# Comim_OBC-v_3_0.net
KiCad netlist of a schematic drawn in EAGLE
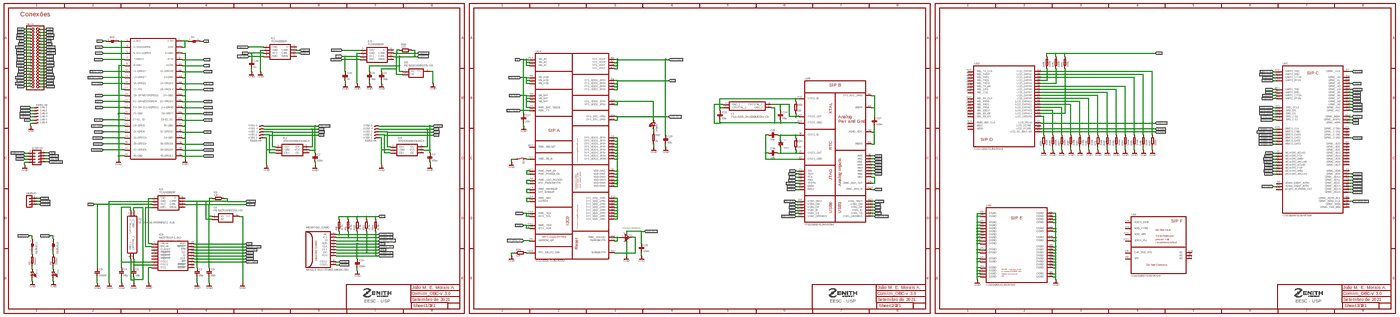
[diagram p0: schematic, sheet 1, overview]
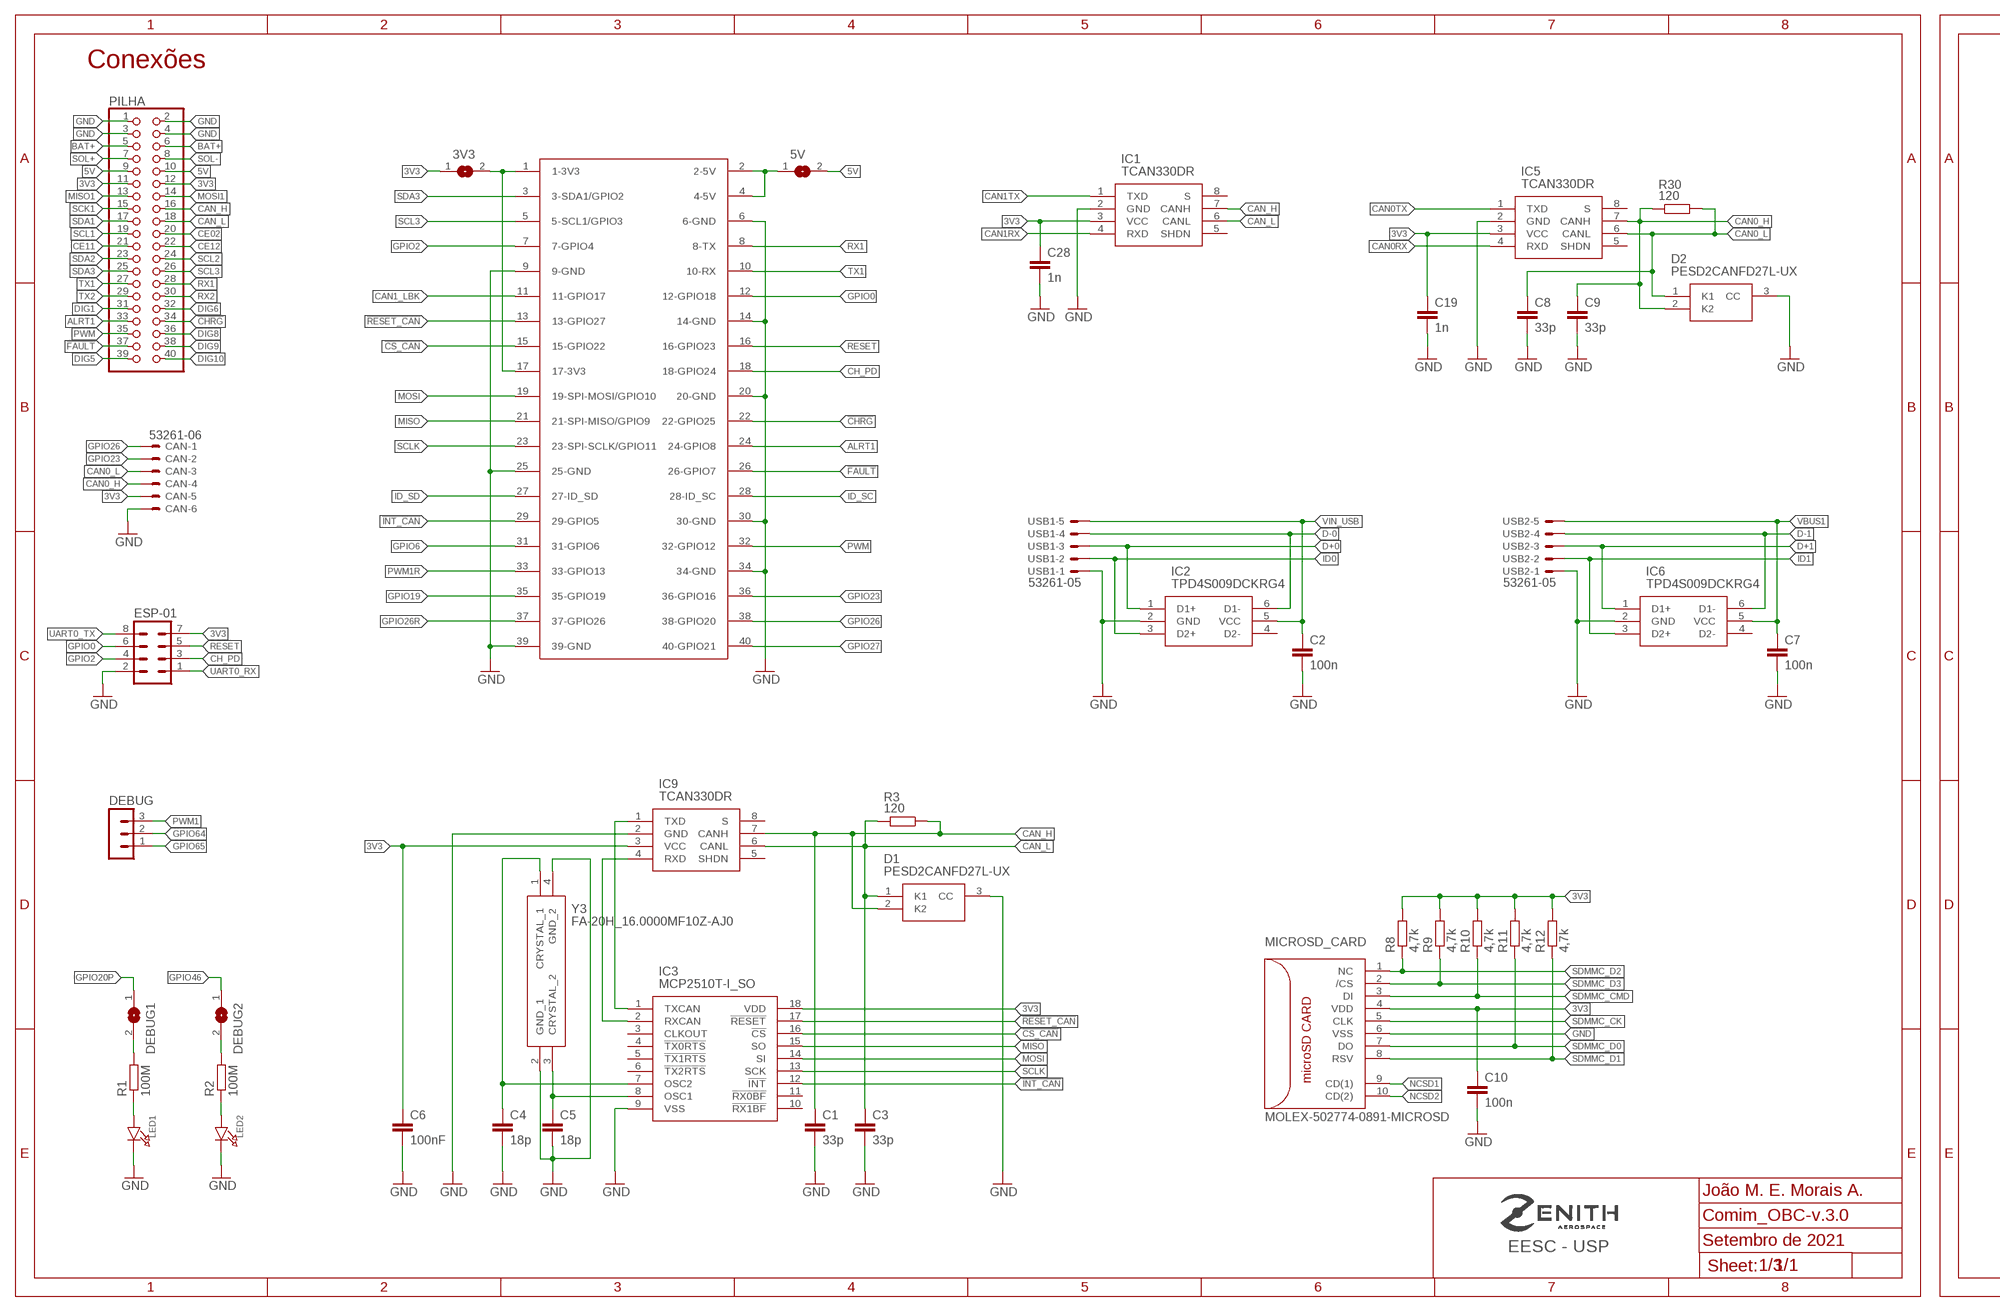
[diagram p1: schematic, sheet 1, part 1 of 4]
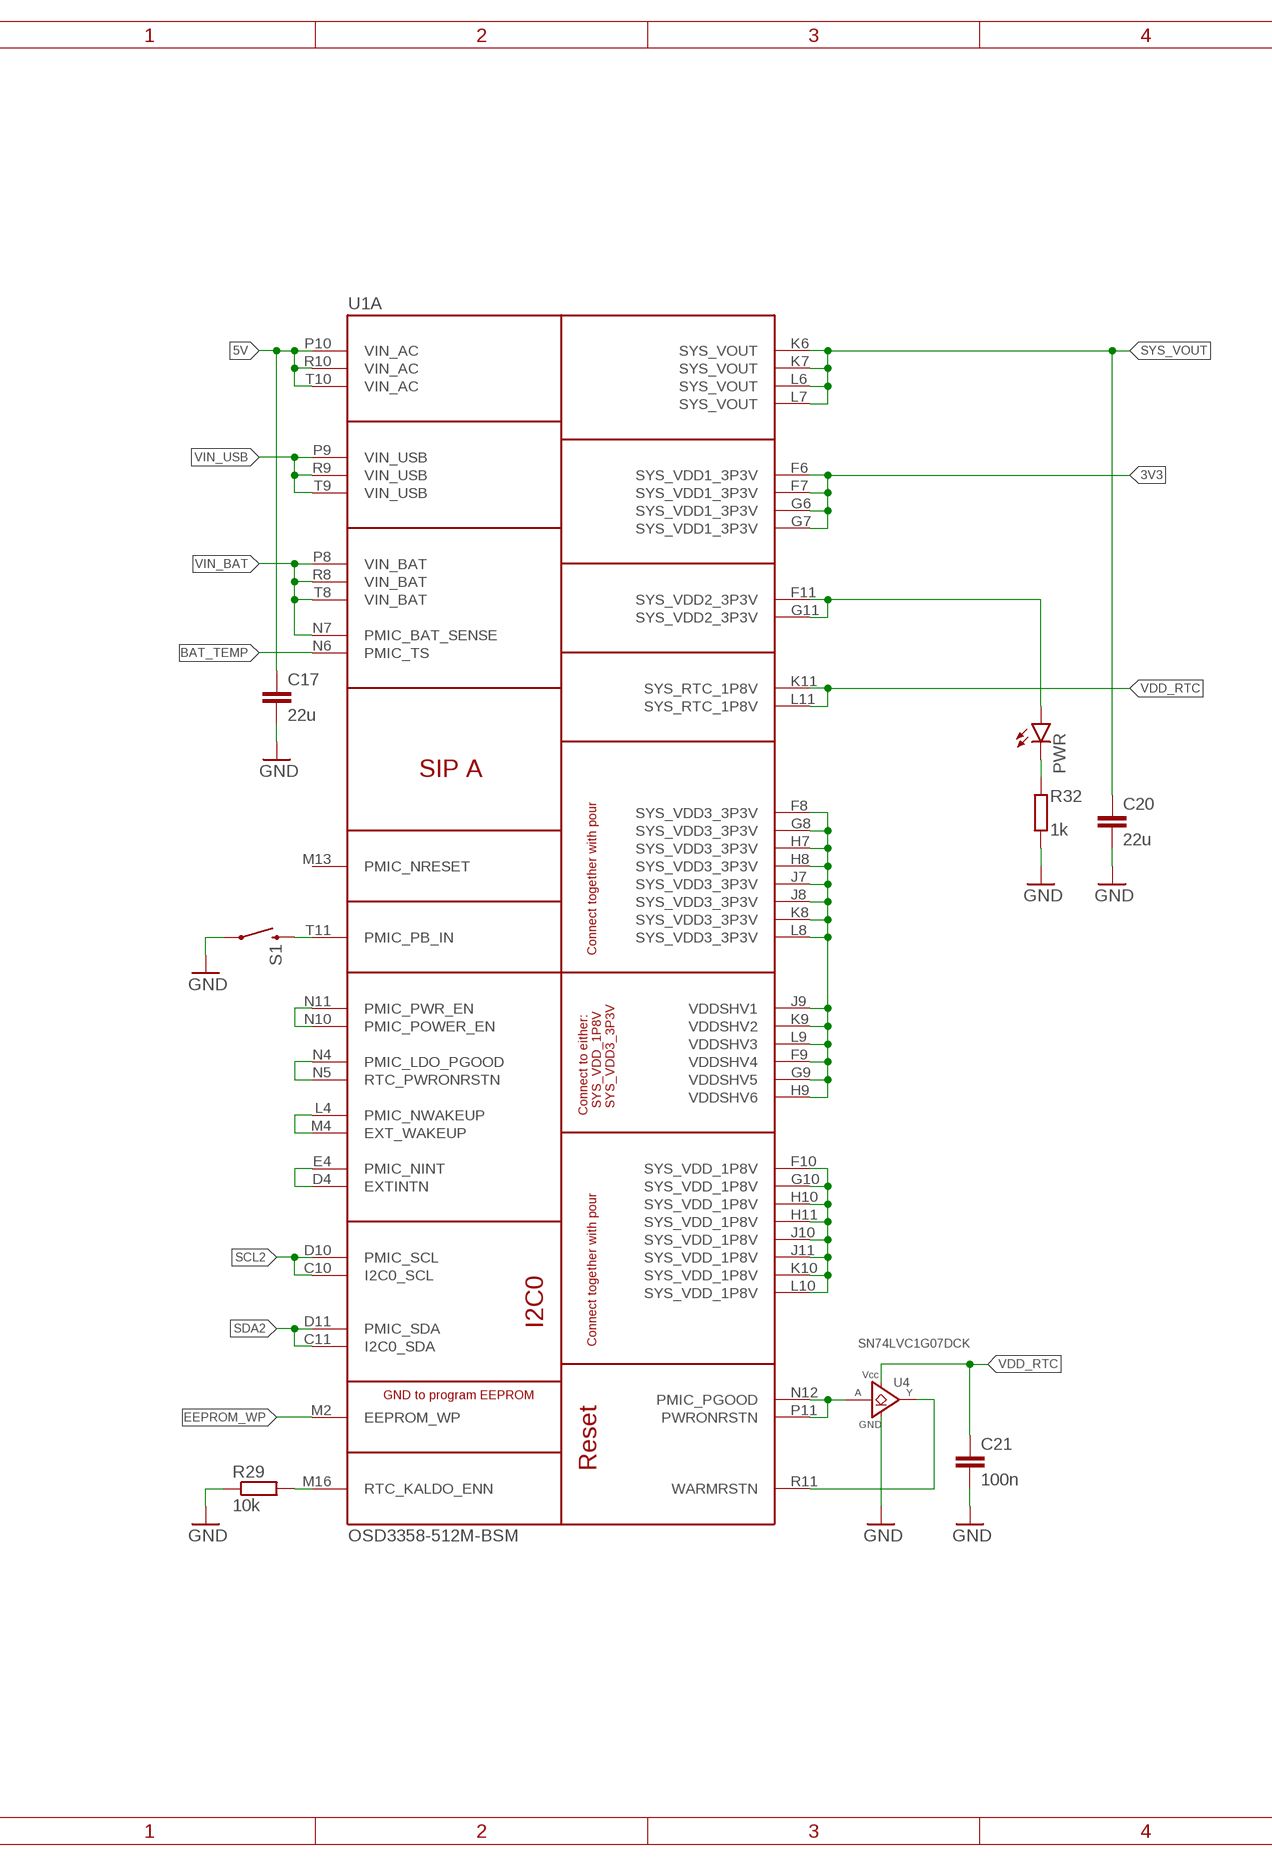
[diagram p2: schematic, sheet 1, part 2 of 4]
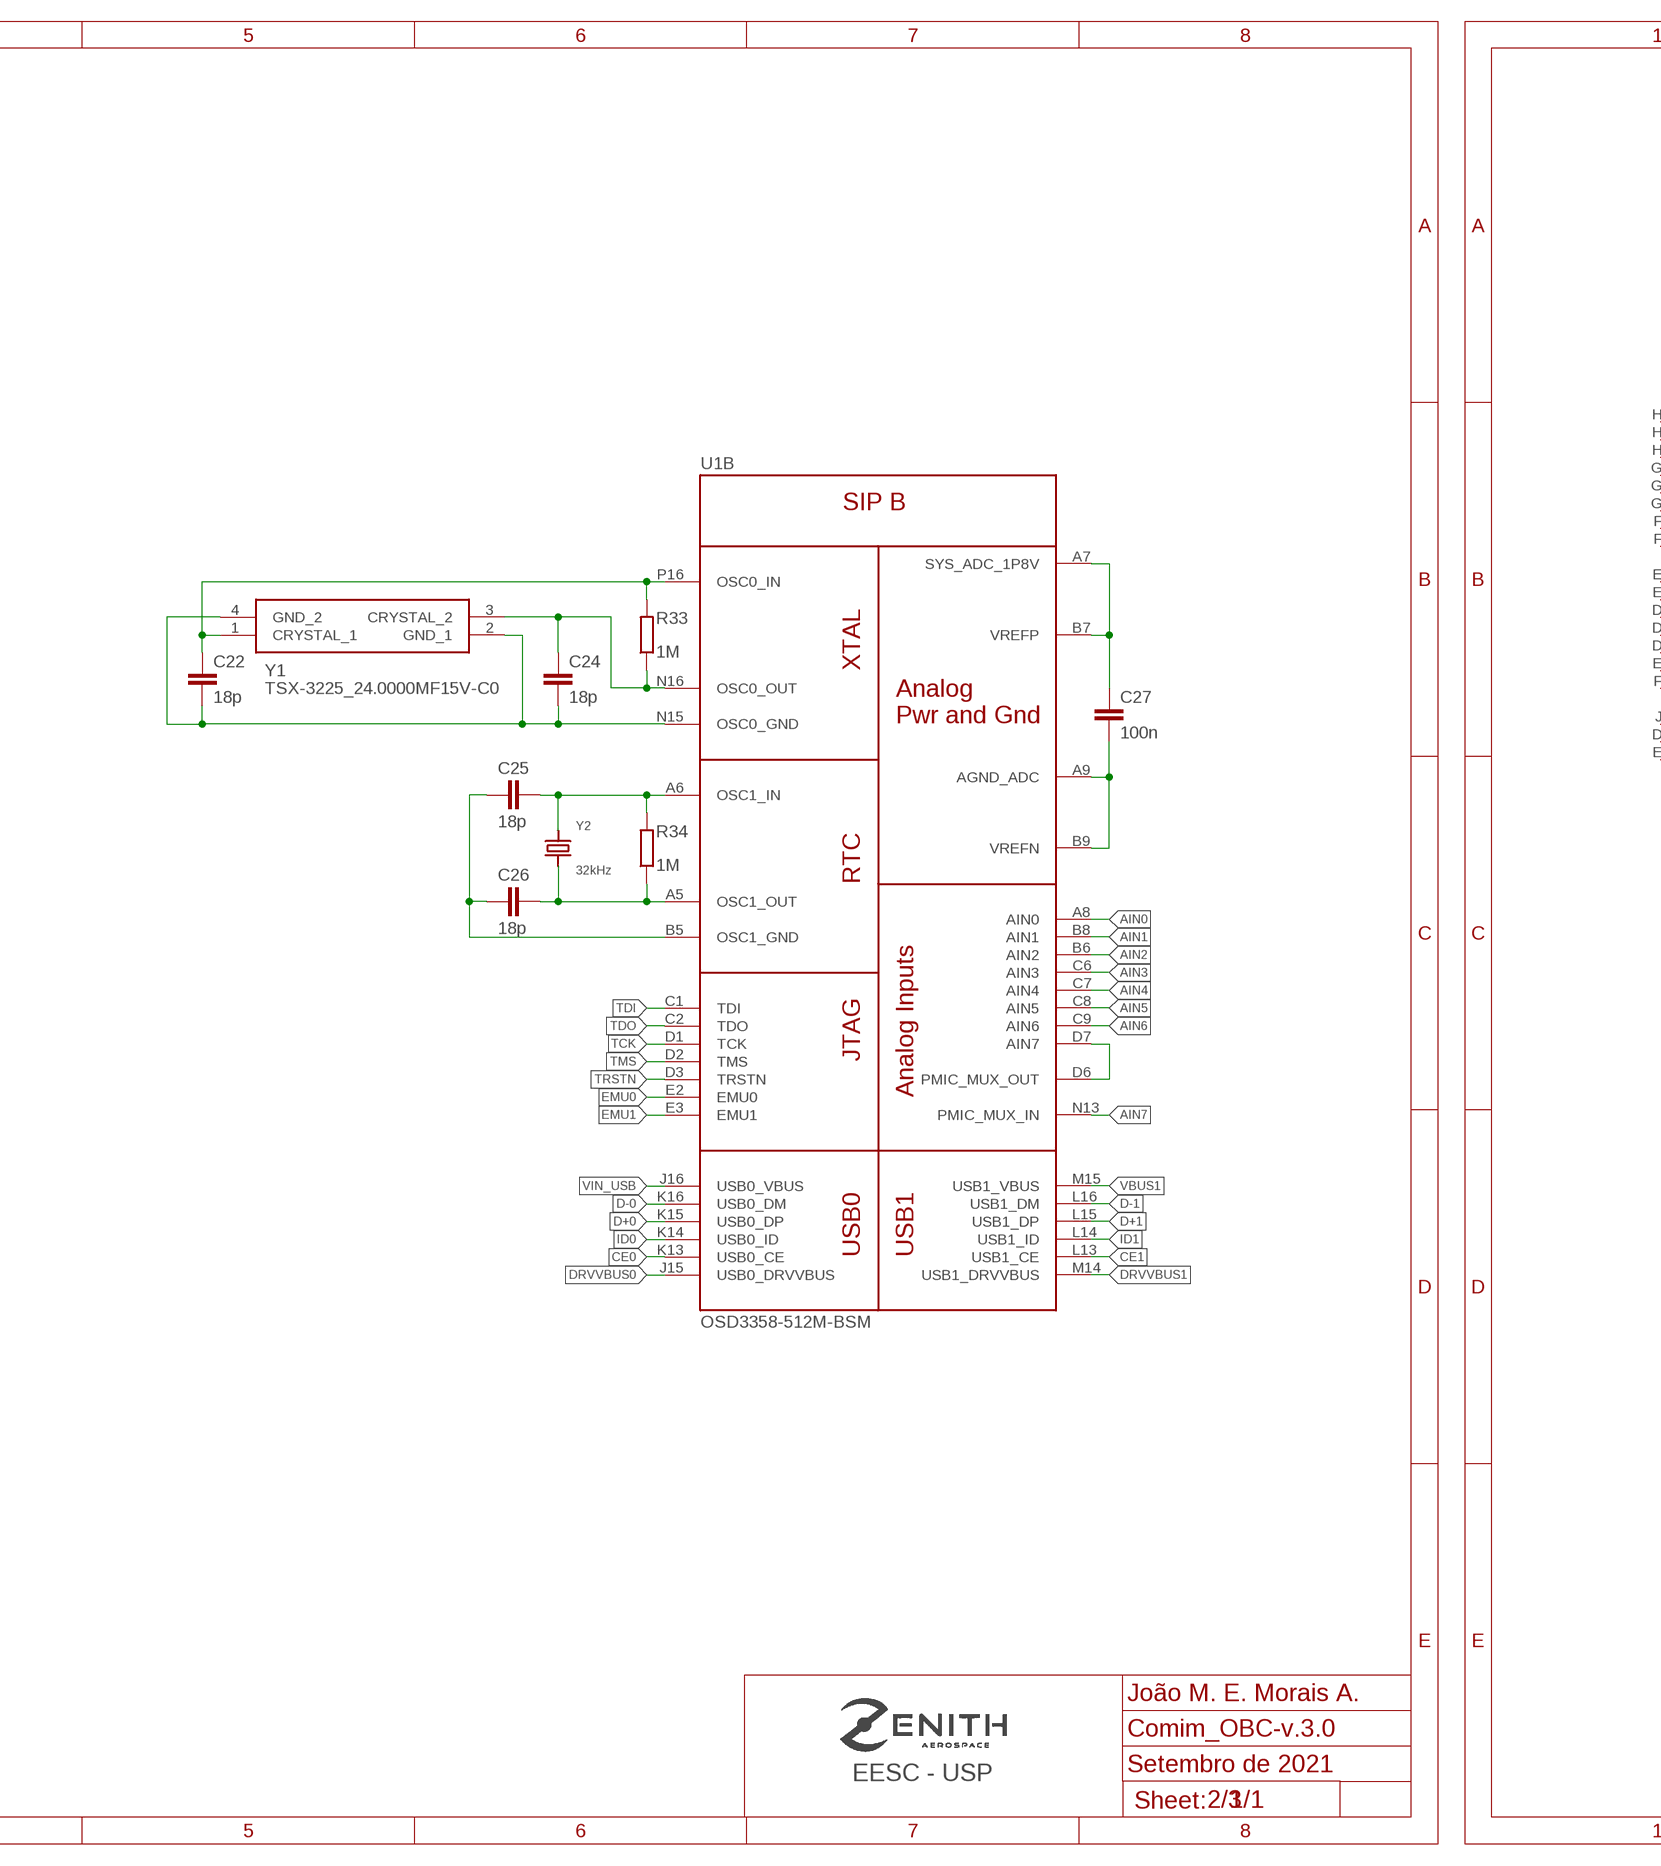
[diagram p3: schematic, sheet 1, part 3 of 4]
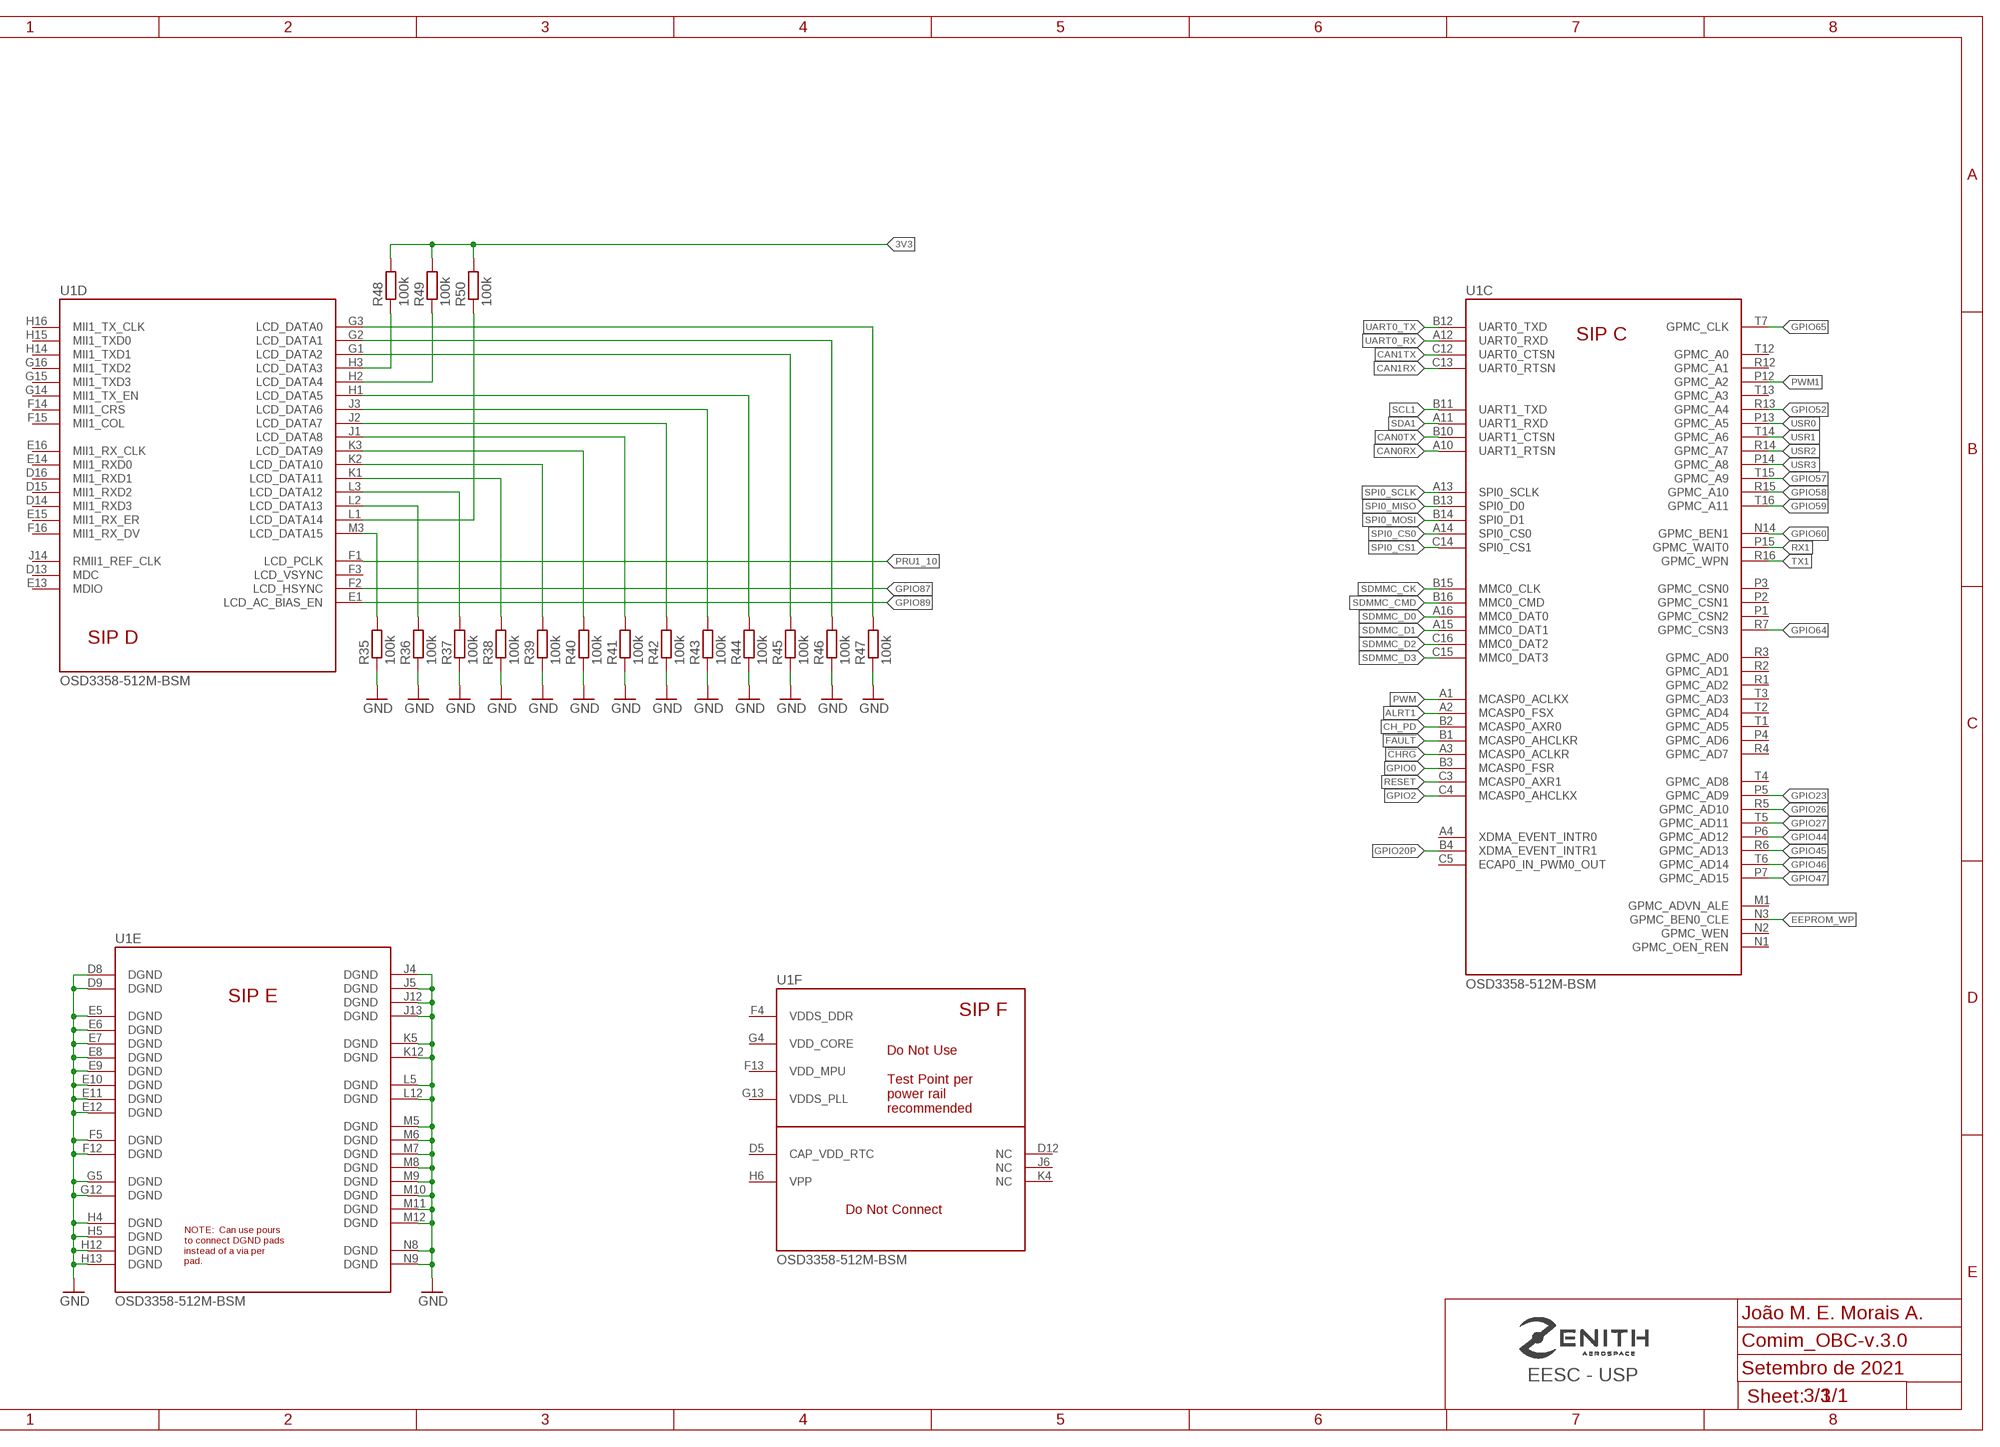
[diagram p4: schematic, sheet 1, part 4 of 4]

(export (version "E")
  (design (tool "Eeschema 10.0.6"))
  (components
    (comp (ref "3V3") (value "SJ") (footprint "eagle-import:SJ") (libsource (lib "eagle-import") (part "SJ")))
    (comp (ref "5V") (value "SJ") (footprint "eagle-import:SJ") (libsource (lib "eagle-import") (part "SJ")))
    (comp (ref "C1")
      (value "33p")
      (footprint "eagle-import:C0805")
      (libsource (lib "eagle-import") (part "C-EUC0805"))
    )
    (comp (ref "C2")
      (value "100n")
      (footprint "eagle-import:C0805")
      (libsource (lib "eagle-import") (part "C-EUC0805"))
    )
    (comp (ref "C3")
      (value "33p")
      (footprint "eagle-import:C0805")
      (libsource (lib "eagle-import") (part "C-EUC0805"))
    )
    (comp (ref "C4")
      (value "18p")
      (footprint "eagle-import:C0805")
      (libsource (lib "eagle-import") (part "C-EUC0805"))
    )
    (comp (ref "C5")
      (value "18p")
      (footprint "eagle-import:C0805")
      (libsource (lib "eagle-import") (part "C-EUC0805"))
    )
    (comp (ref "C6")
      (value "100nF")
      (footprint "eagle-import:C0805")
      (libsource (lib "eagle-import") (part "C-EUC0805"))
    )
    (comp (ref "C7")
      (value "100n")
      (footprint "eagle-import:C0805")
      (libsource (lib "eagle-import") (part "C-EUC0805"))
    )
    (comp (ref "C8")
      (value "33p")
      (footprint "eagle-import:C0805")
      (libsource (lib "eagle-import") (part "C-EUC0805"))
    )
    (comp (ref "C9")
      (value "33p")
      (footprint "eagle-import:C0805")
      (libsource (lib "eagle-import") (part "C-EUC0805"))
    )
    (comp (ref "C10")
      (value "100n")
      (footprint "eagle-import:C0805")
      (libsource (lib "eagle-import") (part "C-EUC0805"))
    )
    (comp (ref "C17")
      (value "22u")
      (footprint "eagle-import:C0805")
      (libsource (lib "eagle-import") (part "C-EUC0805"))
    )
    (comp (ref "C19")
      (value "1n")
      (footprint "eagle-import:C0805")
      (libsource (lib "eagle-import") (part "C-EUC0805"))
    )
    (comp (ref "C20")
      (value "22u")
      (footprint "eagle-import:C0805")
      (libsource (lib "eagle-import") (part "C-EUC0805"))
    )
    (comp (ref "C21")
      (value "100n")
      (footprint "eagle-import:C0805")
      (libsource (lib "eagle-import") (part "C-EUC0805"))
    )
    (comp (ref "C22")
      (value "18p")
      (footprint "eagle-import:C0805")
      (libsource (lib "eagle-import") (part "C-EUC0805"))
    )
    (comp (ref "C24")
      (value "18p")
      (footprint "eagle-import:C0805")
      (libsource (lib "eagle-import") (part "C-EUC0805"))
    )
    (comp (ref "C25")
      (value "18p")
      (footprint "eagle-import:C0805")
      (libsource (lib "eagle-import") (part "C-EUC0805"))
    )
    (comp (ref "C26")
      (value "18p")
      (footprint "eagle-import:C0805")
      (libsource (lib "eagle-import") (part "C-EUC0805"))
    )
    (comp (ref "C27")
      (value "100n")
      (footprint "eagle-import:C0805")
      (libsource (lib "eagle-import") (part "C-EUC0805"))
    )
    (comp (ref "C28")
      (value "1n")
      (footprint "eagle-import:C0805")
      (libsource (lib "eagle-import") (part "C-EUC0805"))
    )
    (comp (ref "CAN")
      (value "53261-06")
      (footprint "eagle-import:53261-06")
      (fields (field (name "MF") "MOLEX"))
      (libsource (lib "eagle-import") (part "53?-06261"))
    )
    (comp (ref "D1")
      (value "PESD2CANFD27L-UX")
      (footprint "eagle-import:SOT65P210X110-3N")
      (fields (field (name "MOUSER_PART_NUMBER") "771-PESD2CANFD27L-UX"))
      (libsource (lib "eagle-import") (part "PESD2CANFD27L-UX"))
    )
    (comp (ref "D2")
      (value "PESD2CANFD27L-UX")
      (footprint "eagle-import:SOT65P210X110-3N")
      (fields (field (name "MOUSER_PART_NUMBER") "771-PESD2CANFD27L-UX"))
      (libsource (lib "eagle-import") (part "PESD2CANFD27L-UX"))
    )
    (comp (ref "DEBUG")
      (value "MA03-1")
      (footprint "eagle-import:MA03-1")
      (libsource (lib "eagle-import") (part "MA03-1"))
    )
    (comp (ref "DEBUG1")
      (value "SOLDERJUMPERREFLOW_NOPASTE")
      (footprint "eagle-import:SOLDERJUMPER_REFLOW_NOPASTE")
      (libsource (lib "eagle-import") (part "SOLDERJUMPERREFLOW_NOPASTE"))
    )
    (comp (ref "DEBUG2")
      (value "SOLDERJUMPERREFLOW_NOPASTE")
      (footprint "eagle-import:SOLDERJUMPER_REFLOW_NOPASTE")
      (libsource (lib "eagle-import") (part "SOLDERJUMPERREFLOW_NOPASTE"))
    )
    (comp (ref "ESP-01")
      (value "MA04-2")
      (footprint "eagle-import:MA04-2")
      (libsource (lib "eagle-import") (part "MA04-2"))
    )
    (comp (ref "IC1")
      (value "TCAN330DR")
      (footprint "eagle-import:SOIC127P600X175-8N")
      (fields (field (name "MOUSER_PART_NUMBER") "595-TCAN330DR"))
      (libsource (lib "eagle-import") (part "TCAN330DR"))
    )
    (comp (ref "IC2")
      (value "TPD4S009DCKRG4")
      (footprint "eagle-import:SOT65P210X110-6N")
      (fields (field (name "MOUSER_PART_NUMBER") "595-TPD4S009DCKRG4"))
      (libsource (lib "eagle-import") (part "TPD4S009DCKRG4"))
    )
    (comp (ref "IC3")
      (value "MCP2510T-I_SO")
      (footprint "eagle-import:SOIC127P1030X265-18N")
      (fields
        (field (name "MANUFACTURER_PART_NUMBER") "MCP2510T-I/SO")
        (field (name "MOUSER_PART_NUMBER") "579-MCP2510T-I/SO")
      )
      (libsource (lib "eagle-import") (part "MCP2510T-I_SO"))
    )
    (comp (ref "IC5")
      (value "TCAN330DR")
      (footprint "eagle-import:SOIC127P600X175-8N")
      (fields (field (name "MOUSER_PART_NUMBER") "595-TCAN330DR"))
      (libsource (lib "eagle-import") (part "TCAN330DR"))
    )
    (comp (ref "IC6")
      (value "TPD4S009DCKRG4")
      (footprint "eagle-import:SOT65P210X110-6N")
      (fields (field (name "MOUSER_PART_NUMBER") "595-TPD4S009DCKRG4"))
      (libsource (lib "eagle-import") (part "TPD4S009DCKRG4"))
    )
    (comp (ref "IC9")
      (value "TCAN330DR")
      (footprint "eagle-import:SOIC127P600X175-8N")
      (fields (field (name "MOUSER_PART_NUMBER") "595-TCAN330DR"))
      (libsource (lib "eagle-import") (part "TCAN330DR"))
    )
    (comp (ref "LED1")
      (value "LED1206")
      (footprint "eagle-import:CHIPLED_1206")
      (libsource (lib "eagle-import") (part "LED1206"))
    )
    (comp (ref "LED2")
      (value "LED1206")
      (footprint "eagle-import:CHIPLED_1206")
      (libsource (lib "eagle-import") (part "LED1206"))
    )
    (comp (ref "MICROSD_CARD")
      (value "MOLEX-502774-0891-MICROSD")
      (footprint "eagle-import:MOLEX-502774-0891-MICROSD")
      (libsource (lib "eagle-import") (part "MOLEX-502774-0891-MICROSD"))
    )
    (comp (ref "PILHA")
      (value "PINHD-2X20")
      (footprint "eagle-import:2X20")
      (libsource (lib "eagle-import") (part "PINHD-2X20"))
    )
    (comp (ref "PWR")
      (value "LEDCHIP-LED0805")
      (footprint "eagle-import:CHIP-LED0805")
      (libsource (lib "eagle-import") (part "LEDCHIP-LED0805"))
    )
    (comp (ref "R1")
      (value "100M")
      (footprint "eagle-import:R0805")
      (libsource (lib "eagle-import") (part "R-EU_R0805"))
    )
    (comp (ref "R2")
      (value "100M")
      (footprint "eagle-import:R0805")
      (libsource (lib "eagle-import") (part "R-EU_R0805"))
    )
    (comp (ref "R3")
      (value "120")
      (footprint "eagle-import:R0805")
      (libsource (lib "eagle-import") (part "R-EU_R0805"))
    )
    (comp (ref "R8")
      (value "4,7k")
      (footprint "eagle-import:R0805")
      (libsource (lib "eagle-import") (part "R-EU_R0805"))
    )
    (comp (ref "R9")
      (value "4,7k")
      (footprint "eagle-import:R0805")
      (libsource (lib "eagle-import") (part "R-EU_R0805"))
    )
    (comp (ref "R10")
      (value "4,7k")
      (footprint "eagle-import:R0805")
      (libsource (lib "eagle-import") (part "R-EU_R0805"))
    )
    (comp (ref "R11")
      (value "4,7k")
      (footprint "eagle-import:R0805")
      (libsource (lib "eagle-import") (part "R-EU_R0805"))
    )
    (comp (ref "R12")
      (value "4,7k")
      (footprint "eagle-import:R0805")
      (libsource (lib "eagle-import") (part "R-EU_R0805"))
    )
    (comp (ref "R29")
      (value "10k")
      (footprint "eagle-import:R0805")
      (libsource (lib "eagle-import") (part "R-EU_R0805"))
    )
    (comp (ref "R30")
      (value "120")
      (footprint "eagle-import:R0805")
      (libsource (lib "eagle-import") (part "R-EU_R0805"))
    )
    (comp (ref "R32")
      (value "1k")
      (footprint "eagle-import:R0805")
      (libsource (lib "eagle-import") (part "R-EU_R0805"))
    )
    (comp (ref "R33")
      (value "1M")
      (footprint "eagle-import:R0805")
      (libsource (lib "eagle-import") (part "R-EU_R0805"))
    )
    (comp (ref "R34")
      (value "1M")
      (footprint "eagle-import:R0805")
      (libsource (lib "eagle-import") (part "R-EU_R0805"))
    )
    (comp (ref "R35")
      (value "100k")
      (footprint "eagle-import:R0805")
      (libsource (lib "eagle-import") (part "R-EU_R0805"))
    )
    (comp (ref "R36")
      (value "100k")
      (footprint "eagle-import:R0805")
      (libsource (lib "eagle-import") (part "R-EU_R0805"))
    )
    (comp (ref "R37")
      (value "100k")
      (footprint "eagle-import:R0805")
      (libsource (lib "eagle-import") (part "R-EU_R0805"))
    )
    (comp (ref "R38")
      (value "100k")
      (footprint "eagle-import:R0805")
      (libsource (lib "eagle-import") (part "R-EU_R0805"))
    )
    (comp (ref "R39")
      (value "100k")
      (footprint "eagle-import:R0805")
      (libsource (lib "eagle-import") (part "R-EU_R0805"))
    )
    (comp (ref "R40")
      (value "100k")
      (footprint "eagle-import:R0805")
      (libsource (lib "eagle-import") (part "R-EU_R0805"))
    )
    (comp (ref "R41")
      (value "100k")
      (footprint "eagle-import:R0805")
      (libsource (lib "eagle-import") (part "R-EU_R0805"))
    )
    (comp (ref "R42")
      (value "100k")
      (footprint "eagle-import:R0805")
      (libsource (lib "eagle-import") (part "R-EU_R0805"))
    )
    (comp (ref "R43")
      (value "100k")
      (footprint "eagle-import:R0805")
      (libsource (lib "eagle-import") (part "R-EU_R0805"))
    )
    (comp (ref "R44")
      (value "100k")
      (footprint "eagle-import:R0805")
      (libsource (lib "eagle-import") (part "R-EU_R0805"))
    )
    (comp (ref "R45")
      (value "100k")
      (footprint "eagle-import:R0805")
      (libsource (lib "eagle-import") (part "R-EU_R0805"))
    )
    (comp (ref "R46")
      (value "100k")
      (footprint "eagle-import:R0805")
      (libsource (lib "eagle-import") (part "R-EU_R0805"))
    )
    (comp (ref "R47")
      (value "100k")
      (footprint "eagle-import:R0805")
      (libsource (lib "eagle-import") (part "R-EU_R0805"))
    )
    (comp (ref "R48")
      (value "100k")
      (footprint "eagle-import:R0805")
      (libsource (lib "eagle-import") (part "R-EU_R0805"))
    )
    (comp (ref "R49")
      (value "100k")
      (footprint "eagle-import:R0805")
      (libsource (lib "eagle-import") (part "R-EU_R0805"))
    )
    (comp (ref "R50")
      (value "100k")
      (footprint "eagle-import:R0805")
      (libsource (lib "eagle-import") (part "R-EU_R0805"))
    )
    (comp (ref "S1")
      (value "MOMENTARY-SWITCH-SPST-SMD-6.0X3.5MM")
      (footprint "eagle-import:TACTILE_SWITCH_SMD_6.0X3.5MM")
      (libsource (lib "eagle-import") (part "MOMENTARY-SWITCH-SPST-SMD-6.0X3.5MM"))
    )
    (comp (ref "U1")
      (value "OSD3358-512M-BSM")
      (footprint "eagle-import:OSD335X-BGA-256")
      (fields (field (name "MFR") "Octavo Systems"))
      (libsource (lib "eagle-import") (part "OSD3358-512M-BSM"))
    )
    (comp (ref "U2")
      (value "RASPBERRY-PI+PIZERO")
      (footprint "eagle-import:RASPBERRY-PI-ZERO")
      (libsource (lib "eagle-import") (part "RASPBERRY-PI+PIZERO"))
    )
    (comp (ref "U4")
      (value "SN74LVC1G07DCK")
      (footprint "eagle-import:SC70(TI-DCK)")
      (libsource (lib "eagle-import") (part "SN74LVC1G07DCK"))
    )
    (comp (ref "USB1")
      (value "53261-05")
      (footprint "eagle-import:53261-05")
      (fields (field (name "MF") "MOLEX"))
      (libsource (lib "eagle-import") (part "53?-05261"))
    )
    (comp (ref "USB2")
      (value "53261-05")
      (footprint "eagle-import:53261-05")
      (fields (field (name "MF") "MOLEX"))
      (libsource (lib "eagle-import") (part "53?-05261"))
    )
    (comp (ref "Y1")
      (value "TSX-3225_24.0000MF15V-C0")
      (footprint "eagle-import:TSX3225240000MF15VC0")
      (fields
        (field (name "MANUFACTURER_PART_NUMBER") "TSX-3225 24.0000MF15V-C0")
        (field (name "MOUSER_PART_NUMBER") "732-22524MF15V-C")
      )
      (libsource (lib "eagle-import") (part "TSX-3225_24.0000MF15V-C0"))
    )
    (comp (ref "Y2")
      (value "32kHz")
      (footprint "eagle-import:CRYSTAL_8X3.8")
      (libsource (lib "eagle-import") (part "CRYSTAL8X3.8SMT"))
    )
    (comp (ref "Y3")
      (value "FA-20H_16.0000MF10Z-AJ0")
      (footprint "eagle-import:FA20H160000MF12ZAC3")
      (fields
        (field (name "MANUFACTURER_PART_NUMBER") "FA-20H 16.0000MF10Z-AJ0")
        (field (name "MOUSER_PART_NUMBER") "732-FA-20H16MF10ZAJ0")
      )
      (libsource (lib "eagle-import") (part "FA-20H_16.0000MF10Z-AJ0"))
    )
  )
  (nets
    (net (code "1") (name "/~{CHRG}") (class "Default")
      (node (ref "PILHA") (pin "34") (pinfunction "34_34") (pintype "passive"))
      (node (ref "U1") (pin "A3") (pinfunction "MCASP0_ACLKR_A3") (pintype "bidirectional"))
      (node (ref "U2") (pin "22") (pinfunction "22-GPIO25_22") (pintype "bidirectional"))
    )
    (net (code "2") (name "/~{CS_CAN}") (class "Default")
      (node (ref "IC3") (pin "16") (pinfunction "~{CS}_16") (pintype "input"))
      (node (ref "U2") (pin "15") (pinfunction "15-GPIO22_15") (pintype "bidirectional"))
    )
    (net (code "3") (name "/~{FAULT}") (class "Default")
      (node (ref "PILHA") (pin "37") (pinfunction "37_37") (pintype "passive"))
      (node (ref "U1") (pin "B1") (pinfunction "MCASP0_AHCLKR_B1") (pintype "bidirectional"))
      (node (ref "U2") (pin "26") (pinfunction "26-GPIO7_26") (pintype "bidirectional"))
    )
    (net (code "4") (name "/~{INT_CAN}") (class "Default")
      (node (ref "IC3") (pin "12") (pinfunction "~{INT}_12") (pintype "input"))
      (node (ref "U2") (pin "29") (pinfunction "29-GPIO5_29") (pintype "bidirectional"))
    )
    (net (code "5") (name "/~{RESET_CAN}") (class "Default")
      (node (ref "IC3") (pin "17") (pinfunction "~{RESET}_17") (pintype "bidirectional"))
      (node (ref "U2") (pin "13") (pinfunction "13-GPIO27_13") (pintype "bidirectional"))
    )
    (net (code "6") (name "3V3") (class "Default")
      (node (ref "3V3") (pin "1") (pinfunction "1_1") (pintype "passive"))
      (node (ref "C10") (pin "1") (pinfunction "1_1") (pintype "passive"))
      (node (ref "C19") (pin "1") (pinfunction "1_1") (pintype "passive"))
      (node (ref "C28") (pin "1") (pinfunction "1_1") (pintype "passive"))
      (node (ref "C6") (pin "1") (pinfunction "1_1") (pintype "passive"))
      (node (ref "CAN") (pin "5") (pinfunction "S_5") (pintype "passive"))
      (node (ref "ESP-01") (pin "7") (pinfunction "7_7") (pintype "passive"))
      (node (ref "IC1") (pin "3") (pinfunction "VCC_3") (pintype "bidirectional"))
      (node (ref "IC3") (pin "18") (pinfunction "VDD_18") (pintype "power_in"))
      (node (ref "IC5") (pin "3") (pinfunction "VCC_3") (pintype "bidirectional"))
      (node (ref "IC9") (pin "3") (pinfunction "VCC_3") (pintype "bidirectional"))
      (node (ref "MICROSD_CARD") (pin "4") (pinfunction "VDD_4") (pintype "bidirectional"))
      (node (ref "PILHA") (pin "11") (pinfunction "11_11") (pintype "passive"))
      (node (ref "PILHA") (pin "12") (pinfunction "12_12") (pintype "passive"))
      (node (ref "R10") (pin "2") (pinfunction "2_2") (pintype "passive"))
      (node (ref "R11") (pin "2") (pinfunction "2_2") (pintype "passive"))
      (node (ref "R12") (pin "2") (pinfunction "2_2") (pintype "passive"))
      (node (ref "R48") (pin "2") (pinfunction "2_2") (pintype "passive"))
      (node (ref "R49") (pin "2") (pinfunction "2_2") (pintype "passive"))
      (node (ref "R50") (pin "2") (pinfunction "2_2") (pintype "passive"))
      (node (ref "R8") (pin "2") (pinfunction "2_2") (pintype "passive"))
      (node (ref "R9") (pin "2") (pinfunction "2_2") (pintype "passive"))
      (node (ref "U1") (pin "F6") (pinfunction "SYS_VDD1_3P3V_F6") (pintype "power_in"))
      (node (ref "U1") (pin "F7") (pinfunction "SYS_VDD1_3P3V_F7") (pintype "power_in"))
      (node (ref "U1") (pin "G6") (pinfunction "SYS_VDD1_3P3V_G6") (pintype "power_in"))
      (node (ref "U1") (pin "G7") (pinfunction "SYS_VDD1_3P3V_G7") (pintype "power_in"))
    )
    (net (code "7") (name "5V") (class "Default")
      (node (ref "5V") (pin "2") (pinfunction "2_2") (pintype "passive"))
      (node (ref "C17") (pin "1") (pinfunction "1_1") (pintype "passive"))
      (node (ref "PILHA") (pin "10") (pinfunction "10_10") (pintype "passive"))
      (node (ref "PILHA") (pin "9") (pinfunction "9_9") (pintype "passive"))
      (node (ref "U1") (pin "P10") (pinfunction "VIN_AC_P10") (pintype "power_in"))
      (node (ref "U1") (pin "R10") (pinfunction "VIN_AC_R10") (pintype "power_in"))
      (node (ref "U1") (pin "T10") (pinfunction "VIN_AC_T10") (pintype "power_in"))
    )
    (net (code "8") (name "AIN0") (class "Default")
      (node (ref "U1") (pin "A8") (pinfunction "AIN0_A8") (pintype "bidirectional"))
    )
    (net (code "9") (name "AIN1") (class "Default")
      (node (ref "U1") (pin "B8") (pinfunction "AIN1_B8") (pintype "bidirectional"))
    )
    (net (code "10") (name "AIN2") (class "Default")
      (node (ref "U1") (pin "B6") (pinfunction "AIN2_B6") (pintype "bidirectional"))
    )
    (net (code "11") (name "AIN3") (class "Default")
      (node (ref "U1") (pin "C6") (pinfunction "AIN3_C6") (pintype "bidirectional"))
    )
    (net (code "12") (name "AIN4") (class "Default")
      (node (ref "U1") (pin "C7") (pinfunction "AIN4_C7") (pintype "bidirectional"))
    )
    (net (code "13") (name "AIN5") (class "Default")
      (node (ref "U1") (pin "C8") (pinfunction "AIN5_C8") (pintype "bidirectional"))
    )
    (net (code "14") (name "AIN6") (class "Default")
      (node (ref "U1") (pin "C9") (pinfunction "AIN6_C9") (pintype "bidirectional"))
    )
    (net (code "15") (name "AIN7") (class "Default")
      (node (ref "U1") (pin "N13") (pinfunction "PMIC_MUX_IN_N13") (pintype "bidirectional"))
    )
    (net (code "16") (name "ALRT1") (class "Default")
      (node (ref "PILHA") (pin "33") (pinfunction "33_33") (pintype "passive"))
      (node (ref "U1") (pin "A2") (pinfunction "MCASP0_FSX_A2") (pintype "bidirectional"))
      (node (ref "U2") (pin "24") (pinfunction "24-GPIO8_24") (pintype "bidirectional"))
    )
    (net (code "17") (name "BAT+") (class "Default")
      (node (ref "PILHA") (pin "5") (pinfunction "5_5") (pintype "passive"))
      (node (ref "PILHA") (pin "6") (pinfunction "6_6") (pintype "passive"))
    )
    (net (code "18") (name "BAT_TEMP") (class "Default")
      (node (ref "U1") (pin "N6") (pinfunction "PMIC_TS_N6") (pintype "bidirectional"))
    )
    (net (code "19") (name "CAN0RX") (class "Default")
      (node (ref "IC5") (pin "4") (pinfunction "RXD_4") (pintype "bidirectional"))
      (node (ref "U1") (pin "A10") (pinfunction "UART1_RTSN_A10") (pintype "bidirectional"))
    )
    (net (code "20") (name "CAN0TX") (class "Default")
      (node (ref "IC5") (pin "1") (pinfunction "TXD_1") (pintype "bidirectional"))
      (node (ref "U1") (pin "B10") (pinfunction "UART1_CTSN_B10") (pintype "bidirectional"))
    )
    (net (code "21") (name "CAN0_H") (class "Default")
      (node (ref "C9") (pin "1") (pinfunction "1_1") (pintype "passive"))
      (node (ref "CAN") (pin "4") (pinfunction "S_4") (pintype "passive"))
      (node (ref "D2") (pin "2") (pinfunction "K2_2") (pintype "bidirectional"))
      (node (ref "IC5") (pin "7") (pinfunction "CANH_7") (pintype "bidirectional"))
      (node (ref "R30") (pin "1") (pinfunction "1_1") (pintype "passive"))
    )
    (net (code "22") (name "CAN0_L") (class "Default")
      (node (ref "C8") (pin "1") (pinfunction "1_1") (pintype "passive"))
      (node (ref "CAN") (pin "3") (pinfunction "S_3") (pintype "passive"))
      (node (ref "D2") (pin "1") (pinfunction "K1_1") (pintype "bidirectional"))
      (node (ref "IC5") (pin "6") (pinfunction "CANL_6") (pintype "bidirectional"))
      (node (ref "R30") (pin "2") (pinfunction "2_2") (pintype "passive"))
    )
    (net (code "23") (name "CAN1RX") (class "Default")
      (node (ref "IC1") (pin "4") (pinfunction "RXD_4") (pintype "bidirectional"))
      (node (ref "U1") (pin "C13") (pinfunction "UART0_RTSN_C13") (pintype "bidirectional"))
    )
    (net (code "24") (name "CAN1TX") (class "Default")
      (node (ref "IC1") (pin "1") (pinfunction "TXD_1") (pintype "bidirectional"))
      (node (ref "U1") (pin "C12") (pinfunction "UART0_CTSN_C12") (pintype "bidirectional"))
    )
    (net (code "25") (name "CAN1_LBK") (class "Default")
      (node (ref "U2") (pin "11") (pinfunction "11-GPIO17_11") (pintype "bidirectional"))
    )
    (net (code "26") (name "CAN_H") (class "Default")
      (node (ref "C1") (pin "1") (pinfunction "1_1") (pintype "passive"))
      (node (ref "D1") (pin "2") (pinfunction "K2_2") (pintype "bidirectional"))
      (node (ref "IC1") (pin "7") (pinfunction "CANH_7") (pintype "bidirectional"))
      (node (ref "IC9") (pin "7") (pinfunction "CANH_7") (pintype "bidirectional"))
      (node (ref "PILHA") (pin "16") (pinfunction "16_16") (pintype "passive"))
      (node (ref "R3") (pin "1") (pinfunction "1_1") (pintype "passive"))
    )
    (net (code "27") (name "CAN_L") (class "Default")
      (node (ref "C3") (pin "1") (pinfunction "1_1") (pintype "passive"))
      (node (ref "D1") (pin "1") (pinfunction "K1_1") (pintype "bidirectional"))
      (node (ref "IC1") (pin "6") (pinfunction "CANL_6") (pintype "bidirectional"))
      (node (ref "IC9") (pin "6") (pinfunction "CANL_6") (pintype "bidirectional"))
      (node (ref "PILHA") (pin "18") (pinfunction "18_18") (pintype "passive"))
      (node (ref "R3") (pin "2") (pinfunction "2_2") (pintype "passive"))
    )
    (net (code "28") (name "CE0") (class "Default")
      (node (ref "U1") (pin "K13") (pinfunction "USB0_CE_K13") (pintype "bidirectional"))
    )
    (net (code "29") (name "CE1") (class "Default")
      (node (ref "U1") (pin "L13") (pinfunction "USB1_CE_L13") (pintype "bidirectional"))
    )
    (net (code "30") (name "CE02") (class "Default")
      (node (ref "PILHA") (pin "20") (pinfunction "20_20") (pintype "passive"))
    )
    (net (code "31") (name "CE11") (class "Default")
      (node (ref "PILHA") (pin "21") (pinfunction "21_21") (pintype "passive"))
    )
    (net (code "32") (name "CE12") (class "Default")
      (node (ref "PILHA") (pin "22") (pinfunction "22_22") (pintype "passive"))
    )
    (net (code "33") (name "CH_PD") (class "Default")
      (node (ref "ESP-01") (pin "3") (pinfunction "3_3") (pintype "passive"))
      (node (ref "U1") (pin "B2") (pinfunction "MCASP0_AXR0_B2") (pintype "bidirectional"))
      (node (ref "U2") (pin "18") (pinfunction "18-GPIO24_18") (pintype "bidirectional"))
    )
    (net (code "34") (name "D+0") (class "Default")
      (node (ref "IC2") (pin "1") (pinfunction "D1+_1") (pintype "bidirectional"))
      (node (ref "U1") (pin "K15") (pinfunction "USB0_DP_K15") (pintype "bidirectional"))
      (node (ref "USB1") (pin "3") (pinfunction "S_3") (pintype "passive"))
    )
    (net (code "35") (name "D+1") (class "Default")
      (node (ref "IC6") (pin "1") (pinfunction "D1+_1") (pintype "bidirectional"))
      (node (ref "U1") (pin "L15") (pinfunction "USB1_DP_L15") (pintype "bidirectional"))
      (node (ref "USB2") (pin "3") (pinfunction "S_3") (pintype "passive"))
    )
    (net (code "36") (name "D-0") (class "Default")
      (node (ref "IC2") (pin "6") (pinfunction "D1-_6") (pintype "bidirectional"))
      (node (ref "U1") (pin "K16") (pinfunction "USB0_DM_K16") (pintype "bidirectional"))
      (node (ref "USB1") (pin "4") (pinfunction "S_4") (pintype "passive"))
    )
    (net (code "37") (name "D-1") (class "Default")
      (node (ref "IC6") (pin "6") (pinfunction "D1-_6") (pintype "bidirectional"))
      (node (ref "U1") (pin "L16") (pinfunction "USB1_DM_L16") (pintype "bidirectional"))
      (node (ref "USB2") (pin "4") (pinfunction "S_4") (pintype "passive"))
    )
    (net (code "38") (name "DIG1") (class "Default")
      (node (ref "PILHA") (pin "31") (pinfunction "31_31") (pintype "passive"))
    )
    (net (code "39") (name "DIG5") (class "Default")
      (node (ref "PILHA") (pin "39") (pinfunction "39_39") (pintype "passive"))
    )
    (net (code "40") (name "DIG6") (class "Default")
      (node (ref "PILHA") (pin "32") (pinfunction "32_32") (pintype "passive"))
    )
    (net (code "41") (name "DIG8") (class "Default")
      (node (ref "PILHA") (pin "36") (pinfunction "36_36") (pintype "passive"))
    )
    (net (code "42") (name "DIG9") (class "Default")
      (node (ref "PILHA") (pin "38") (pinfunction "38_38") (pintype "passive"))
    )
    (net (code "43") (name "DIG10") (class "Default")
      (node (ref "PILHA") (pin "40") (pinfunction "40_40") (pintype "passive"))
    )
    (net (code "44") (name "DRVVBUS0") (class "Default")
      (node (ref "U1") (pin "J15") (pinfunction "USB0_DRVVBUS_J15") (pintype "bidirectional"))
    )
    (net (code "45") (name "DRVVBUS1") (class "Default")
      (node (ref "U1") (pin "M14") (pinfunction "USB1_DRVVBUS_M14") (pintype "bidirectional"))
    )
    (net (code "46") (name "EEPROM_WP") (class "Default")
      (node (ref "U1") (pin "M2") (pinfunction "EEPROM_WP_M2") (pintype "bidirectional"))
      (node (ref "U1") (pin "N3") (pinfunction "GPMC_BEN0_CLE_N3") (pintype "bidirectional"))
    )
    (net (code "47") (name "EMU0") (class "Default")
      (node (ref "U1") (pin "E2") (pinfunction "EMU0_E2") (pintype "bidirectional"))
    )
    (net (code "48") (name "EMU1") (class "Default")
      (node (ref "U1") (pin "E3") (pinfunction "EMU1_E3") (pintype "bidirectional"))
    )
    (net (code "49") (name "GND") (class "Default")
      (node (ref "C1") (pin "2") (pinfunction "2_2") (pintype "passive"))
      (node (ref "C10") (pin "2") (pinfunction "2_2") (pintype "passive"))
      (node (ref "C17") (pin "2") (pinfunction "2_2") (pintype "passive"))
      (node (ref "C19") (pin "2") (pinfunction "2_2") (pintype "passive"))
      (node (ref "C2") (pin "2") (pinfunction "2_2") (pintype "passive"))
      (node (ref "C20") (pin "2") (pinfunction "2_2") (pintype "passive"))
      (node (ref "C21") (pin "2") (pinfunction "2_2") (pintype "passive"))
      (node (ref "C28") (pin "2") (pinfunction "2_2") (pintype "passive"))
      (node (ref "C3") (pin "2") (pinfunction "2_2") (pintype "passive"))
      (node (ref "C4") (pin "2") (pinfunction "2_2") (pintype "passive"))
      (node (ref "C5") (pin "2") (pinfunction "2_2") (pintype "passive"))
      (node (ref "C6") (pin "2") (pinfunction "2_2") (pintype "passive"))
      (node (ref "C7") (pin "2") (pinfunction "2_2") (pintype "passive"))
      (node (ref "C8") (pin "2") (pinfunction "2_2") (pintype "passive"))
      (node (ref "C9") (pin "2") (pinfunction "2_2") (pintype "passive"))
      (node (ref "CAN") (pin "6") (pinfunction "S_6") (pintype "passive"))
      (node (ref "D1") (pin "3") (pinfunction "CC_3") (pintype "bidirectional"))
      (node (ref "D2") (pin "3") (pinfunction "CC_3") (pintype "bidirectional"))
      (node (ref "ESP-01") (pin "2") (pinfunction "2_2") (pintype "passive"))
      (node (ref "IC1") (pin "2") (pinfunction "GND_2") (pintype "bidirectional"))
      (node (ref "IC2") (pin "2") (pinfunction "GND_2") (pintype "bidirectional"))
      (node (ref "IC3") (pin "9") (pinfunction "VSS_9") (pintype "power_in"))
      (node (ref "IC5") (pin "2") (pinfunction "GND_2") (pintype "bidirectional"))
      (node (ref "IC6") (pin "2") (pinfunction "GND_2") (pintype "bidirectional"))
      (node (ref "IC9") (pin "2") (pinfunction "GND_2") (pintype "bidirectional"))
      (node (ref "LED1") (pin "C") (pinfunction "C_C") (pintype "passive"))
      (node (ref "LED2") (pin "C") (pinfunction "C_C") (pintype "passive"))
      (node (ref "MICROSD_CARD") (pin "6") (pinfunction "VSS_6") (pintype "bidirectional"))
      (node (ref "PILHA") (pin "1") (pinfunction "1_1") (pintype "passive"))
      (node (ref "PILHA") (pin "2") (pinfunction "2_2") (pintype "passive"))
      (node (ref "PILHA") (pin "3") (pinfunction "3_3") (pintype "passive"))
      (node (ref "PILHA") (pin "4") (pinfunction "4_4") (pintype "passive"))
      (node (ref "R29") (pin "1") (pinfunction "1_1") (pintype "passive"))
      (node (ref "R32") (pin "1") (pinfunction "1_1") (pintype "passive"))
      (node (ref "R35") (pin "1") (pinfunction "1_1") (pintype "passive"))
      (node (ref "R36") (pin "1") (pinfunction "1_1") (pintype "passive"))
      (node (ref "R37") (pin "1") (pinfunction "1_1") (pintype "passive"))
      (node (ref "R38") (pin "1") (pinfunction "1_1") (pintype "passive"))
      (node (ref "R39") (pin "1") (pinfunction "1_1") (pintype "passive"))
      (node (ref "R40") (pin "1") (pinfunction "1_1") (pintype "passive"))
      (node (ref "R41") (pin "1") (pinfunction "1_1") (pintype "passive"))
      (node (ref "R42") (pin "1") (pinfunction "1_1") (pintype "passive"))
      (node (ref "R43") (pin "1") (pinfunction "1_1") (pintype "passive"))
      (node (ref "R44") (pin "1") (pinfunction "1_1") (pintype "passive"))
      (node (ref "R45") (pin "1") (pinfunction "1_1") (pintype "passive"))
      (node (ref "R46") (pin "1") (pinfunction "1_1") (pintype "passive"))
      (node (ref "R47") (pin "1") (pinfunction "1_1") (pintype "passive"))
      (node (ref "S1") (pin "1") (pinfunction "1_1") (pintype "passive"))
      (node (ref "U1") (pin "D8") (pinfunction "DGND_D8") (pintype "bidirectional"))
      (node (ref "U1") (pin "D9") (pinfunction "DGND_D9") (pintype "bidirectional"))
      (node (ref "U1") (pin "E10") (pinfunction "DGND_E10") (pintype "bidirectional"))
      (node (ref "U1") (pin "E11") (pinfunction "DGND_E11") (pintype "bidirectional"))
      (node (ref "U1") (pin "E12") (pinfunction "DGND_E12") (pintype "bidirectional"))
      (node (ref "U1") (pin "E5") (pinfunction "DGND_E5") (pintype "bidirectional"))
      (node (ref "U1") (pin "E6") (pinfunction "DGND_E6") (pintype "bidirectional"))
      (node (ref "U1") (pin "E7") (pinfunction "DGND_E7") (pintype "bidirectional"))
      (node (ref "U1") (pin "E8") (pinfunction "DGND_E8") (pintype "bidirectional"))
      (node (ref "U1") (pin "E9") (pinfunction "DGND_E9") (pintype "bidirectional"))
      (node (ref "U1") (pin "F12") (pinfunction "DGND_F12") (pintype "bidirectional"))
      (node (ref "U1") (pin "F5") (pinfunction "DGND_F5") (pintype "bidirectional"))
      (node (ref "U1") (pin "G12") (pinfunction "DGND_G12") (pintype "bidirectional"))
      (node (ref "U1") (pin "G5") (pinfunction "DGND_G5") (pintype "bidirectional"))
      (node (ref "U1") (pin "H12") (pinfunction "DGND_H12") (pintype "bidirectional"))
      (node (ref "U1") (pin "H13") (pinfunction "DGND_H13") (pintype "bidirectional"))
      (node (ref "U1") (pin "H4") (pinfunction "DGND_H4") (pintype "bidirectional"))
      (node (ref "U1") (pin "H5") (pinfunction "DGND_H5") (pintype "bidirectional"))
      (node (ref "U1") (pin "J12") (pinfunction "DGND_J12") (pintype "bidirectional"))
      (node (ref "U1") (pin "J13") (pinfunction "DGND_J13") (pintype "bidirectional"))
      (node (ref "U1") (pin "J4") (pinfunction "DGND_J4") (pintype "bidirectional"))
      (node (ref "U1") (pin "J5") (pinfunction "DGND_J5") (pintype "bidirectional"))
      (node (ref "U1") (pin "K12") (pinfunction "DGND_K12") (pintype "bidirectional"))
      (node (ref "U1") (pin "K5") (pinfunction "DGND_K5") (pintype "bidirectional"))
      (node (ref "U1") (pin "L12") (pinfunction "DGND_L12") (pintype "bidirectional"))
      (node (ref "U1") (pin "L5") (pinfunction "DGND_L5") (pintype "bidirectional"))
      (node (ref "U1") (pin "M10") (pinfunction "DGND_M10") (pintype "bidirectional"))
      (node (ref "U1") (pin "M11") (pinfunction "DGND_M11") (pintype "bidirectional"))
      (node (ref "U1") (pin "M12") (pinfunction "DGND_M12") (pintype "bidirectional"))
      (node (ref "U1") (pin "M5") (pinfunction "DGND_M5") (pintype "bidirectional"))
      (node (ref "U1") (pin "M6") (pinfunction "DGND_M6") (pintype "bidirectional"))
      (node (ref "U1") (pin "M7") (pinfunction "DGND_M7") (pintype "bidirectional"))
      (node (ref "U1") (pin "M8") (pinfunction "DGND_M8") (pintype "bidirectional"))
      (node (ref "U1") (pin "M9") (pinfunction "DGND_M9") (pintype "bidirectional"))
      (node (ref "U1") (pin "N8") (pinfunction "DGND_N8") (pintype "bidirectional"))
      (node (ref "U1") (pin "N9") (pinfunction "DGND_N9") (pintype "bidirectional"))
      (node (ref "U2") (pin "14") (pinfunction "14-GND_14") (pintype "bidirectional"))
      (node (ref "U2") (pin "20") (pinfunction "20-GND_20") (pintype "bidirectional"))
      (node (ref "U2") (pin "25") (pinfunction "25-GND_25") (pintype "bidirectional"))
      (node (ref "U2") (pin "30") (pinfunction "30-GND_30") (pintype "bidirectional"))
      (node (ref "U2") (pin "34") (pinfunction "34-GND_34") (pintype "bidirectional"))
      (node (ref "U2") (pin "39") (pinfunction "39-GND_39") (pintype "bidirectional"))
      (node (ref "U2") (pin "6") (pinfunction "6-GND_6") (pintype "bidirectional"))
      (node (ref "U2") (pin "9") (pinfunction "9-GND_9") (pintype "bidirectional"))
      (node (ref "U4") (pin "3") (pinfunction "GND_3") (pintype "bidirectional"))
      (node (ref "USB1") (pin "1") (pinfunction "S_1") (pintype "passive"))
      (node (ref "USB2") (pin "1") (pinfunction "S_1") (pintype "passive"))
      (node (ref "Y3") (pin "2") (pinfunction "GND_1_2") (pintype "bidirectional"))
      (node (ref "Y3") (pin "4") (pinfunction "GND_2_4") (pintype "bidirectional"))
    )
    (net (code "50") (name "GPIO0") (class "Default")
      (node (ref "ESP-01") (pin "6") (pinfunction "6_6") (pintype "passive"))
      (node (ref "U1") (pin "B3") (pinfunction "MCASP0_FSR_B3") (pintype "bidirectional"))
      (node (ref "U2") (pin "12") (pinfunction "12-GPIO18_12") (pintype "bidirectional"))
    )
    (net (code "51") (name "GPIO2") (class "Default")
      (node (ref "ESP-01") (pin "4") (pinfunction "4_4") (pintype "passive"))
      (node (ref "U1") (pin "C4") (pinfunction "MCASP0_AHCLKX_C4") (pintype "bidirectional"))
      (node (ref "U2") (pin "7") (pinfunction "7-GPIO4_7") (pintype "bidirectional"))
    )
    (net (code "52") (name "GPIO6") (class "Default")
      (node (ref "U2") (pin "31") (pinfunction "31-GPIO6_31") (pintype "bidirectional"))
    )
    (net (code "53") (name "GPIO19") (class "Default")
      (node (ref "U2") (pin "35") (pinfunction "35-GPIO19_35") (pintype "bidirectional"))
    )
    (net (code "54") (name "GPIO20P") (class "Default")
      (node (ref "DEBUG1") (pin "1") (pinfunction "1_1") (pintype "passive"))
      (node (ref "U1") (pin "B4") (pinfunction "XDMA_EVENT_INTR1_B4") (pintype "bidirectional"))
    )
    (net (code "55") (name "GPIO23") (class "Default")
      (node (ref "CAN") (pin "2") (pinfunction "S_2") (pintype "passive"))
      (node (ref "U1") (pin "P5") (pinfunction "GPMC_AD9_P5") (pintype "bidirectional"))
      (node (ref "U2") (pin "36") (pinfunction "36-GPIO16_36") (pintype "bidirectional"))
    )
    (net (code "56") (name "GPIO26") (class "Default")
      (node (ref "CAN") (pin "1") (pinfunction "S_1") (pintype "passive"))
      (node (ref "U1") (pin "R5") (pinfunction "GPMC_AD10_R5") (pintype "bidirectional"))
      (node (ref "U2") (pin "38") (pinfunction "38-GPIO20_38") (pintype "bidirectional"))
    )
    (net (code "57") (name "GPIO26R") (class "Default")
      (node (ref "U2") (pin "37") (pinfunction "37-GPIO26_37") (pintype "bidirectional"))
    )
    (net (code "58") (name "GPIO27") (class "Default")
      (node (ref "U1") (pin "T5") (pinfunction "GPMC_AD11_T5") (pintype "bidirectional"))
      (node (ref "U2") (pin "40") (pinfunction "40-GPIO21_40") (pintype "bidirectional"))
    )
    (net (code "59") (name "GPIO44") (class "Default")
      (node (ref "U1") (pin "P6") (pinfunction "GPMC_AD12_P6") (pintype "bidirectional"))
    )
    (net (code "60") (name "GPIO45") (class "Default")
      (node (ref "U1") (pin "R6") (pinfunction "GPMC_AD13_R6") (pintype "bidirectional"))
    )
    (net (code "61") (name "GPIO46") (class "Default")
      (node (ref "DEBUG2") (pin "1") (pinfunction "1_1") (pintype "passive"))
      (node (ref "U1") (pin "T6") (pinfunction "GPMC_AD14_T6") (pintype "bidirectional"))
    )
    (net (code "62") (name "GPIO47") (class "Default")
      (node (ref "U1") (pin "P7") (pinfunction "GPMC_AD15_P7") (pintype "bidirectional"))
    )
    (net (code "63") (name "GPIO52") (class "Default")
      (node (ref "U1") (pin "R13") (pinfunction "GPMC_A4_R13") (pintype "bidirectional"))
    )
    (net (code "64") (name "GPIO57") (class "Default")
      (node (ref "U1") (pin "T15") (pinfunction "GPMC_A9_T15") (pintype "bidirectional"))
    )
    (net (code "65") (name "GPIO58") (class "Default")
      (node (ref "U1") (pin "R15") (pinfunction "GPMC_A10_R15") (pintype "bidirectional"))
    )
    (net (code "66") (name "GPIO59") (class "Default")
      (node (ref "U1") (pin "T16") (pinfunction "GPMC_A11_T16") (pintype "bidirectional"))
    )
    (net (code "67") (name "GPIO60") (class "Default")
      (node (ref "U1") (pin "N14") (pinfunction "GPMC_BEN1_N14") (pintype "bidirectional"))
    )
    (net (code "68") (name "GPIO64") (class "Default")
      (node (ref "DEBUG") (pin "2") (pinfunction "2_2") (pintype "passive"))
      (node (ref "U1") (pin "R7") (pinfunction "GPMC_CSN3_R7") (pintype "bidirectional"))
    )
    (net (code "69") (name "GPIO65") (class "Default")
      (node (ref "DEBUG") (pin "1") (pinfunction "1_1") (pintype "passive"))
      (node (ref "U1") (pin "T7") (pinfunction "GPMC_CLK_T7") (pintype "bidirectional"))
    )
    (net (code "70") (name "GPIO87") (class "Default")
      (node (ref "U1") (pin "F2") (pinfunction "LCD_HSYNC_F2") (pintype "bidirectional"))
    )
    (net (code "71") (name "GPIO89") (class "Default")
      (node (ref "U1") (pin "E1") (pinfunction "LCD_AC_BIAS_EN_E1") (pintype "bidirectional"))
    )
    (net (code "72") (name "ID0") (class "Default")
      (node (ref "IC2") (pin "3") (pinfunction "D2+_3") (pintype "bidirectional"))
      (node (ref "U1") (pin "K14") (pinfunction "USB0_ID_K14") (pintype "bidirectional"))
      (node (ref "USB1") (pin "2") (pinfunction "S_2") (pintype "passive"))
    )
    (net (code "73") (name "ID1") (class "Default")
      (node (ref "IC6") (pin "3") (pinfunction "D2+_3") (pintype "bidirectional"))
      (node (ref "U1") (pin "L14") (pinfunction "USB1_ID_L14") (pintype "bidirectional"))
      (node (ref "USB2") (pin "2") (pinfunction "S_2") (pintype "passive"))
    )
    (net (code "74") (name "ID_SC") (class "Default")
      (node (ref "U2") (pin "28") (pinfunction "28-ID_SC_28") (pintype "bidirectional"))
    )
    (net (code "75") (name "ID_SD") (class "Default")
      (node (ref "U2") (pin "27") (pinfunction "27-ID_SD_27") (pintype "bidirectional"))
    )
    (net (code "76") (name "MISO") (class "Default")
      (node (ref "IC3") (pin "15") (pinfunction "SO_15") (pintype "bidirectional"))
      (node (ref "U2") (pin "21") (pinfunction "21-SPI-MISO/GPIO9_21") (pintype "bidirectional"))
    )
    (net (code "77") (name "MISO1") (class "Default")
      (node (ref "PILHA") (pin "13") (pinfunction "13_13") (pintype "passive"))
    )
    (net (code "78") (name "MOSI") (class "Default")
      (node (ref "IC3") (pin "14") (pinfunction "SI_14") (pintype "bidirectional"))
      (node (ref "U2") (pin "19") (pinfunction "19-SPI-MOSI/GPIO10_19") (pintype "bidirectional"))
    )
    (net (code "79") (name "MOSI1") (class "Default")
      (node (ref "PILHA") (pin "14") (pinfunction "14_14") (pintype "passive"))
    )
    (net (code "80") (name "NCSD1") (class "Default")
      (node (ref "MICROSD_CARD") (pin "9") (pinfunction "CD(1)_9") (pintype "bidirectional"))
    )
    (net (code "81") (name "NCSD2") (class "Default")
      (node (ref "MICROSD_CARD") (pin "10") (pinfunction "CD(2)_10") (pintype "bidirectional"))
    )
    (net (code "82") (name "Net-(DEBUG1-Pad2)") (class "Default")
      (node (ref "DEBUG1") (pin "2") (pinfunction "2_2") (pintype "passive"))
      (node (ref "R1") (pin "2") (pinfunction "2_2") (pintype "passive"))
    )
    (net (code "83") (name "Net-(DEBUG2-Pad2)") (class "Default")
      (node (ref "DEBUG2") (pin "2") (pinfunction "2_2") (pintype "passive"))
      (node (ref "R2") (pin "2") (pinfunction "2_2") (pintype "passive"))
    )
    (net (code "84") (name "Net-(IC3-OSC1)") (class "Default")
      (node (ref "C5") (pin "1") (pinfunction "1_1") (pintype "passive"))
      (node (ref "IC3") (pin "8") (pinfunction "OSC1_8") (pintype "bidirectional"))
      (node (ref "Y3") (pin "3") (pinfunction "CRYSTAL_2_3") (pintype "bidirectional"))
    )
    (net (code "85") (name "Net-(IC3-OSC2)") (class "Default")
      (node (ref "C4") (pin "1") (pinfunction "1_1") (pintype "passive"))
      (node (ref "IC3") (pin "7") (pinfunction "OSC2_7") (pintype "bidirectional"))
      (node (ref "Y3") (pin "1") (pinfunction "CRYSTAL_1_1") (pintype "bidirectional"))
    )
    (net (code "86") (name "Net-(IC3-RXCAN)") (class "Default")
      (node (ref "IC3") (pin "2") (pinfunction "RXCAN_2") (pintype "bidirectional"))
      (node (ref "IC9") (pin "4") (pinfunction "RXD_4") (pintype "bidirectional"))
    )
    (net (code "87") (name "Net-(IC3-TXCAN)") (class "Default")
      (node (ref "IC3") (pin "1") (pinfunction "TXCAN_1") (pintype "bidirectional"))
      (node (ref "IC9") (pin "1") (pinfunction "TXD_1") (pintype "bidirectional"))
    )
    (net (code "88") (name "Net-(LED1-PadA)") (class "Default")
      (node (ref "LED1") (pin "A") (pinfunction "A_A") (pintype "passive"))
      (node (ref "R1") (pin "1") (pinfunction "1_1") (pintype "passive"))
    )
    (net (code "89") (name "Net-(LED2-PadA)") (class "Default")
      (node (ref "LED2") (pin "A") (pinfunction "A_A") (pintype "passive"))
      (node (ref "R2") (pin "1") (pinfunction "1_1") (pintype "passive"))
    )
    (net (code "90") (name "Net-(PWR-PadA)") (class "Default")
      (node (ref "PWR") (pin "A") (pinfunction "A_A") (pintype "passive"))
      (node (ref "U1") (pin "F11") (pinfunction "SYS_VDD2_3P3V_F11") (pintype "power_in"))
      (node (ref "U1") (pin "G11") (pinfunction "SYS_VDD2_3P3V_G11") (pintype "power_in"))
    )
    (net (code "91") (name "Net-(PWR-PadC)") (class "Default")
      (node (ref "PWR") (pin "C") (pinfunction "C_C") (pintype "passive"))
      (node (ref "R32") (pin "2") (pinfunction "2_2") (pintype "passive"))
    )
    (net (code "92") (name "Net-(U1A-EXTINTN)") (class "Default")
      (node (ref "U1") (pin "D4") (pinfunction "EXTINTN_D4") (pintype "bidirectional"))
      (node (ref "U1") (pin "E4") (pinfunction "PMIC_NINT_E4") (pintype "output"))
    )
    (net (code "93") (name "Net-(U1A-EXT_WAKEUP)") (class "Default")
      (node (ref "U1") (pin "L4") (pinfunction "PMIC_NWAKEUP_L4") (pintype "output"))
      (node (ref "U1") (pin "M4") (pinfunction "EXT_WAKEUP_M4") (pintype "bidirectional"))
    )
    (net (code "94") (name "Net-(U1A-PMIC_LDO_PGOOD)") (class "Default")
      (node (ref "U1") (pin "N4") (pinfunction "PMIC_LDO_PGOOD_N4") (pintype "output"))
      (node (ref "U1") (pin "N5") (pinfunction "RTC_PWRONRSTN_N5") (pintype "bidirectional"))
    )
    (net (code "95") (name "Net-(U1A-PMIC_PB_IN)") (class "Default")
      (node (ref "S1") (pin "2") (pinfunction "2_2") (pintype "passive"))
      (node (ref "U1") (pin "T11") (pinfunction "PMIC_PB_IN_T11") (pintype "bidirectional"))
    )
    (net (code "96") (name "Net-(U1A-PMIC_PGOOD)") (class "Default")
      (node (ref "U1") (pin "N12") (pinfunction "PMIC_PGOOD_N12") (pintype "output"))
      (node (ref "U1") (pin "P11") (pinfunction "PWRONRSTN_P11") (pintype "bidirectional"))
      (node (ref "U4") (pin "2") (pinfunction "A_2") (pintype "bidirectional"))
    )
    (net (code "97") (name "Net-(U1A-PMIC_POWER_EN)") (class "Default")
      (node (ref "U1") (pin "N10") (pinfunction "PMIC_POWER_EN_N10") (pintype "output"))
      (node (ref "U1") (pin "N11") (pinfunction "PMIC_PWR_EN_N11") (pintype "input"))
    )
    (net (code "98") (name "Net-(U1A-RTC_KALDO_ENN)") (class "Default")
      (node (ref "R29") (pin "2") (pinfunction "2_2") (pintype "passive"))
      (node (ref "U1") (pin "M16") (pinfunction "RTC_KALDO_ENN_M16") (pintype "bidirectional"))
    )
    (net (code "99") (name "Net-(U1A-SYS_VDD_1P8V-PadF10)") (class "Default")
      (node (ref "U1") (pin "F10") (pinfunction "SYS_VDD_1P8V_F10") (pintype "power_in"))
      (node (ref "U1") (pin "G10") (pinfunction "SYS_VDD_1P8V_G10") (pintype "power_in"))
      (node (ref "U1") (pin "H10") (pinfunction "SYS_VDD_1P8V_H10") (pintype "power_in"))
      (node (ref "U1") (pin "H11") (pinfunction "SYS_VDD_1P8V_H11") (pintype "power_in"))
      (node (ref "U1") (pin "J10") (pinfunction "SYS_VDD_1P8V_J10") (pintype "power_in"))
      (node (ref "U1") (pin "J11") (pinfunction "SYS_VDD_1P8V_J11") (pintype "power_in"))
      (node (ref "U1") (pin "K10") (pinfunction "SYS_VDD_1P8V_K10") (pintype "power_in"))
      (node (ref "U1") (pin "L10") (pinfunction "SYS_VDD_1P8V_L10") (pintype "power_in"))
    )
    (net (code "100") (name "Net-(U1A-VDDSHV1)") (class "Default")
      (node (ref "U1") (pin "F8") (pinfunction "SYS_VDD3_3P3V_F8") (pintype "power_in"))
      (node (ref "U1") (pin "F9") (pinfunction "VDDSHV4_F9") (pintype "power_in"))
      (node (ref "U1") (pin "G8") (pinfunction "SYS_VDD3_3P3V_G8") (pintype "power_in"))
      (node (ref "U1") (pin "G9") (pinfunction "VDDSHV5_G9") (pintype "power_in"))
      (node (ref "U1") (pin "H7") (pinfunction "SYS_VDD3_3P3V_H7") (pintype "power_in"))
      (node (ref "U1") (pin "H8") (pinfunction "SYS_VDD3_3P3V_H8") (pintype "power_in"))
      (node (ref "U1") (pin "H9") (pinfunction "VDDSHV6_H9") (pintype "power_in"))
      (node (ref "U1") (pin "J7") (pinfunction "SYS_VDD3_3P3V_J7") (pintype "power_in"))
      (node (ref "U1") (pin "J8") (pinfunction "SYS_VDD3_3P3V_J8") (pintype "power_in"))
      (node (ref "U1") (pin "J9") (pinfunction "VDDSHV1_J9") (pintype "power_in"))
      (node (ref "U1") (pin "K8") (pinfunction "SYS_VDD3_3P3V_K8") (pintype "power_in"))
      (node (ref "U1") (pin "K9") (pinfunction "VDDSHV2_K9") (pintype "power_in"))
      (node (ref "U1") (pin "L8") (pinfunction "SYS_VDD3_3P3V_L8") (pintype "power_in"))
      (node (ref "U1") (pin "L9") (pinfunction "VDDSHV3_L9") (pintype "power_in"))
    )
    (net (code "101") (name "Net-(U1A-WARMRSTN)") (class "Default")
      (node (ref "U1") (pin "R11") (pinfunction "WARMRSTN_R11") (pintype "bidirectional"))
      (node (ref "U4") (pin "4") (pinfunction "Y_4") (pintype "bidirectional"))
    )
    (net (code "102") (name "Net-(U1B-AGND_ADC)") (class "Default")
      (node (ref "C27") (pin "2") (pinfunction "2_2") (pintype "passive"))
      (node (ref "U1") (pin "A9") (pinfunction "AGND_ADC_A9") (pintype "bidirectional"))
      (node (ref "U1") (pin "B9") (pinfunction "VREFN_B9") (pintype "bidirectional"))
    )
    (net (code "103") (name "Net-(U1B-AIN7)") (class "Default")
      (node (ref "U1") (pin "D6") (pinfunction "PMIC_MUX_OUT_D6") (pintype "bidirectional"))
      (node (ref "U1") (pin "D7") (pinfunction "AIN7_D7") (pintype "bidirectional"))
    )
    (net (code "104") (name "Net-(U1B-OSC0_GND)") (class "Default")
      (node (ref "C22") (pin "2") (pinfunction "2_2") (pintype "passive"))
      (node (ref "C24") (pin "2") (pinfunction "2_2") (pintype "passive"))
      (node (ref "U1") (pin "N15") (pinfunction "OSC0_GND_N15") (pintype "bidirectional"))
      (node (ref "Y1") (pin "2") (pinfunction "GND_1_2") (pintype "bidirectional"))
      (node (ref "Y1") (pin "4") (pinfunction "GND_2_4") (pintype "bidirectional"))
    )
    (net (code "105") (name "Net-(U1B-OSC0_IN)") (class "Default")
      (node (ref "C22") (pin "1") (pinfunction "1_1") (pintype "passive"))
      (node (ref "R33") (pin "2") (pinfunction "2_2") (pintype "passive"))
      (node (ref "U1") (pin "P16") (pinfunction "OSC0_IN_P16") (pintype "bidirectional"))
      (node (ref "Y1") (pin "1") (pinfunction "CRYSTAL_1_1") (pintype "bidirectional"))
    )
    (net (code "106") (name "Net-(U1B-OSC0_OUT)") (class "Default")
      (node (ref "C24") (pin "1") (pinfunction "1_1") (pintype "passive"))
      (node (ref "R33") (pin "1") (pinfunction "1_1") (pintype "passive"))
      (node (ref "U1") (pin "N16") (pinfunction "OSC0_OUT_N16") (pintype "bidirectional"))
      (node (ref "Y1") (pin "3") (pinfunction "CRYSTAL_2_3") (pintype "bidirectional"))
    )
    (net (code "107") (name "Net-(U1B-OSC1_GND)") (class "Default")
      (node (ref "C25") (pin "2") (pinfunction "2_2") (pintype "passive"))
      (node (ref "C26") (pin "2") (pinfunction "2_2") (pintype "passive"))
      (node (ref "U1") (pin "B5") (pinfunction "OSC1_GND_B5") (pintype "bidirectional"))
    )
    (net (code "108") (name "Net-(U1B-OSC1_IN)") (class "Default")
      (node (ref "C25") (pin "1") (pinfunction "1_1") (pintype "passive"))
      (node (ref "R34") (pin "2") (pinfunction "2_2") (pintype "passive"))
      (node (ref "U1") (pin "A6") (pinfunction "OSC1_IN_A6") (pintype "bidirectional"))
      (node (ref "Y2") (pin "P$1") (pinfunction "1_P$1") (pintype "passive"))
    )
    (net (code "109") (name "Net-(U1B-OSC1_OUT)") (class "Default")
      (node (ref "C26") (pin "1") (pinfunction "1_1") (pintype "passive"))
      (node (ref "R34") (pin "1") (pinfunction "1_1") (pintype "passive"))
      (node (ref "U1") (pin "A5") (pinfunction "OSC1_OUT_A5") (pintype "bidirectional"))
      (node (ref "Y2") (pin "P$4") (pinfunction "2_P$4") (pintype "passive"))
    )
    (net (code "110") (name "Net-(U1B-SYS_ADC_1P8V)") (class "Default")
      (node (ref "C27") (pin "1") (pinfunction "1_1") (pintype "passive"))
      (node (ref "U1") (pin "A7") (pinfunction "SYS_ADC_1P8V_A7") (pintype "bidirectional"))
      (node (ref "U1") (pin "B7") (pinfunction "VREFP_B7") (pintype "bidirectional"))
    )
    (net (code "111") (name "Net-(U1D-LCD_DATA0)") (class "Default")
      (node (ref "R47") (pin "2") (pinfunction "2_2") (pintype "passive"))
      (node (ref "U1") (pin "G3") (pinfunction "LCD_DATA0_G3") (pintype "bidirectional"))
    )
    (net (code "112") (name "Net-(U1D-LCD_DATA1)") (class "Default")
      (node (ref "R46") (pin "2") (pinfunction "2_2") (pintype "passive"))
      (node (ref "U1") (pin "G2") (pinfunction "LCD_DATA1_G2") (pintype "bidirectional"))
    )
    (net (code "113") (name "Net-(U1D-LCD_DATA2)") (class "Default")
      (node (ref "R45") (pin "2") (pinfunction "2_2") (pintype "passive"))
      (node (ref "U1") (pin "G1") (pinfunction "LCD_DATA2_G1") (pintype "bidirectional"))
    )
    (net (code "114") (name "Net-(U1D-LCD_DATA3)") (class "Default")
      (node (ref "R48") (pin "1") (pinfunction "1_1") (pintype "passive"))
      (node (ref "U1") (pin "H3") (pinfunction "LCD_DATA3_H3") (pintype "bidirectional"))
    )
    (net (code "115") (name "Net-(U1D-LCD_DATA4)") (class "Default")
      (node (ref "R49") (pin "1") (pinfunction "1_1") (pintype "passive"))
      (node (ref "U1") (pin "H2") (pinfunction "LCD_DATA4_H2") (pintype "bidirectional"))
    )
    (net (code "116") (name "Net-(U1D-LCD_DATA5)") (class "Default")
      (node (ref "R44") (pin "2") (pinfunction "2_2") (pintype "passive"))
      (node (ref "U1") (pin "H1") (pinfunction "LCD_DATA5_H1") (pintype "bidirectional"))
    )
    (net (code "117") (name "Net-(U1D-LCD_DATA6)") (class "Default")
      (node (ref "R43") (pin "2") (pinfunction "2_2") (pintype "passive"))
      (node (ref "U1") (pin "J3") (pinfunction "LCD_DATA6_J3") (pintype "bidirectional"))
    )
    (net (code "118") (name "Net-(U1D-LCD_DATA7)") (class "Default")
      (node (ref "R42") (pin "2") (pinfunction "2_2") (pintype "passive"))
      (node (ref "U1") (pin "J2") (pinfunction "LCD_DATA7_J2") (pintype "bidirectional"))
    )
    (net (code "119") (name "Net-(U1D-LCD_DATA8)") (class "Default")
      (node (ref "R41") (pin "2") (pinfunction "2_2") (pintype "passive"))
      (node (ref "U1") (pin "J1") (pinfunction "LCD_DATA8_J1") (pintype "bidirectional"))
    )
    (net (code "120") (name "Net-(U1D-LCD_DATA9)") (class "Default")
      (node (ref "R40") (pin "2") (pinfunction "2_2") (pintype "passive"))
      (node (ref "U1") (pin "K3") (pinfunction "LCD_DATA9_K3") (pintype "bidirectional"))
    )
    (net (code "121") (name "Net-(U1D-LCD_DATA10)") (class "Default")
      (node (ref "R39") (pin "2") (pinfunction "2_2") (pintype "passive"))
      (node (ref "U1") (pin "K2") (pinfunction "LCD_DATA10_K2") (pintype "bidirectional"))
    )
    (net (code "122") (name "Net-(U1D-LCD_DATA11)") (class "Default")
      (node (ref "R38") (pin "2") (pinfunction "2_2") (pintype "passive"))
      (node (ref "U1") (pin "K1") (pinfunction "LCD_DATA11_K1") (pintype "bidirectional"))
    )
    (net (code "123") (name "Net-(U1D-LCD_DATA12)") (class "Default")
      (node (ref "R37") (pin "2") (pinfunction "2_2") (pintype "passive"))
      (node (ref "U1") (pin "L3") (pinfunction "LCD_DATA12_L3") (pintype "bidirectional"))
    )
    (net (code "124") (name "Net-(U1D-LCD_DATA13)") (class "Default")
      (node (ref "R36") (pin "2") (pinfunction "2_2") (pintype "passive"))
      (node (ref "U1") (pin "L2") (pinfunction "LCD_DATA13_L2") (pintype "bidirectional"))
    )
    (net (code "125") (name "Net-(U1D-LCD_DATA14)") (class "Default")
      (node (ref "R50") (pin "1") (pinfunction "1_1") (pintype "passive"))
      (node (ref "U1") (pin "L1") (pinfunction "LCD_DATA14_L1") (pintype "bidirectional"))
    )
    (net (code "126") (name "Net-(U1D-LCD_DATA15)") (class "Default")
      (node (ref "R35") (pin "2") (pinfunction "2_2") (pintype "passive"))
      (node (ref "U1") (pin "M3") (pinfunction "LCD_DATA15_M3") (pintype "bidirectional"))
    )
    (net (code "127") (name "Net-(U2-1-3V3)") (class "Default")
      (node (ref "3V3") (pin "2") (pinfunction "2_2") (pintype "passive"))
      (node (ref "U2") (pin "1") (pinfunction "1-3V3_1") (pintype "bidirectional"))
      (node (ref "U2") (pin "17") (pinfunction "17-3V3_17") (pintype "bidirectional"))
    )
    (net (code "128") (name "Net-(U2-2-5V)") (class "Default")
      (node (ref "5V") (pin "1") (pinfunction "1_1") (pintype "passive"))
      (node (ref "U2") (pin "2") (pinfunction "2-5V_2") (pintype "bidirectional"))
      (node (ref "U2") (pin "4") (pinfunction "4-5V_4") (pintype "bidirectional"))
    )
    (net (code "129") (name "PRU1_10") (class "Default")
      (node (ref "U1") (pin "F1") (pinfunction "LCD_PCLK_F1") (pintype "bidirectional"))
    )
    (net (code "130") (name "PWM") (class "Default")
      (node (ref "PILHA") (pin "35") (pinfunction "35_35") (pintype "passive"))
      (node (ref "U1") (pin "A1") (pinfunction "MCASP0_ACLKX_A1") (pintype "bidirectional"))
      (node (ref "U2") (pin "32") (pinfunction "32-GPIO12_32") (pintype "bidirectional"))
    )
    (net (code "131") (name "PWM1") (class "Default")
      (node (ref "DEBUG") (pin "3") (pinfunction "3_3") (pintype "passive"))
      (node (ref "U1") (pin "P12") (pinfunction "GPMC_A2_P12") (pintype "bidirectional"))
    )
    (net (code "132") (name "PWM1R") (class "Default")
      (node (ref "U2") (pin "33") (pinfunction "33-GPIO13_33") (pintype "bidirectional"))
    )
    (net (code "133") (name "RESET") (class "Default")
      (node (ref "ESP-01") (pin "5") (pinfunction "5_5") (pintype "passive"))
      (node (ref "U1") (pin "C3") (pinfunction "MCASP0_AXR1_C3") (pintype "bidirectional"))
      (node (ref "U2") (pin "16") (pinfunction "16-GPIO23_16") (pintype "bidirectional"))
    )
    (net (code "134") (name "RX1") (class "Default")
      (node (ref "PILHA") (pin "28") (pinfunction "28_28") (pintype "passive"))
      (node (ref "U1") (pin "P15") (pinfunction "GPMC_WAIT0_P15") (pintype "bidirectional"))
      (node (ref "U2") (pin "8") (pinfunction "8-TX_8") (pintype "bidirectional"))
    )
    (net (code "135") (name "RX2") (class "Default")
      (node (ref "PILHA") (pin "30") (pinfunction "30_30") (pintype "passive"))
    )
    (net (code "136") (name "SCK1") (class "Default")
      (node (ref "PILHA") (pin "15") (pinfunction "15_15") (pintype "passive"))
    )
    (net (code "137") (name "SCL1") (class "Default")
      (node (ref "PILHA") (pin "19") (pinfunction "19_19") (pintype "passive"))
      (node (ref "U1") (pin "B11") (pinfunction "UART1_TXD_B11") (pintype "bidirectional"))
    )
    (net (code "138") (name "SCL2") (class "Default")
      (node (ref "PILHA") (pin "24") (pinfunction "24_24") (pintype "passive"))
      (node (ref "U1") (pin "C10") (pinfunction "I2C0_SCL_C10") (pintype "bidirectional"))
      (node (ref "U1") (pin "D10") (pinfunction "PMIC_SCL_D10") (pintype "bidirectional"))
    )
    (net (code "139") (name "SCL3") (class "Default")
      (node (ref "PILHA") (pin "26") (pinfunction "26_26") (pintype "passive"))
      (node (ref "U2") (pin "5") (pinfunction "5-SCL1/GPIO3_5") (pintype "bidirectional"))
    )
    (net (code "140") (name "SCLK") (class "Default")
      (node (ref "IC3") (pin "13") (pinfunction "SCK_13") (pintype "bidirectional"))
      (node (ref "U2") (pin "23") (pinfunction "23-SPI-SCLK/GPIO11_23") (pintype "bidirectional"))
    )
    (net (code "141") (name "SDA1") (class "Default")
      (node (ref "PILHA") (pin "17") (pinfunction "17_17") (pintype "passive"))
      (node (ref "U1") (pin "A11") (pinfunction "UART1_RXD_A11") (pintype "bidirectional"))
    )
    (net (code "142") (name "SDA2") (class "Default")
      (node (ref "PILHA") (pin "23") (pinfunction "23_23") (pintype "passive"))
      (node (ref "U1") (pin "C11") (pinfunction "I2C0_SDA_C11") (pintype "bidirectional"))
      (node (ref "U1") (pin "D11") (pinfunction "PMIC_SDA_D11") (pintype "bidirectional"))
    )
    (net (code "143") (name "SDA3") (class "Default")
      (node (ref "PILHA") (pin "25") (pinfunction "25_25") (pintype "passive"))
      (node (ref "U2") (pin "3") (pinfunction "3-SDA1/GPIO2_3") (pintype "bidirectional"))
    )
    (net (code "144") (name "SDMMC_CK") (class "Default")
      (node (ref "MICROSD_CARD") (pin "5") (pinfunction "CLK_5") (pintype "bidirectional"))
      (node (ref "U1") (pin "B15") (pinfunction "MMC0_CLK_B15") (pintype "bidirectional"))
    )
    (net (code "145") (name "SDMMC_CMD") (class "Default")
      (node (ref "MICROSD_CARD") (pin "3") (pinfunction "DI_3") (pintype "bidirectional"))
      (node (ref "R10") (pin "1") (pinfunction "1_1") (pintype "passive"))
      (node (ref "U1") (pin "B16") (pinfunction "MMC0_CMD_B16") (pintype "bidirectional"))
    )
    (net (code "146") (name "SDMMC_D0") (class "Default")
      (node (ref "MICROSD_CARD") (pin "7") (pinfunction "DO_7") (pintype "bidirectional"))
      (node (ref "R11") (pin "1") (pinfunction "1_1") (pintype "passive"))
      (node (ref "U1") (pin "A16") (pinfunction "MMC0_DAT0_A16") (pintype "bidirectional"))
    )
    (net (code "147") (name "SDMMC_D1") (class "Default")
      (node (ref "MICROSD_CARD") (pin "8") (pinfunction "RSV_8") (pintype "bidirectional"))
      (node (ref "R12") (pin "1") (pinfunction "1_1") (pintype "passive"))
      (node (ref "U1") (pin "A15") (pinfunction "MMC0_DAT1_A15") (pintype "bidirectional"))
    )
    (net (code "148") (name "SDMMC_D2") (class "Default")
      (node (ref "MICROSD_CARD") (pin "1") (pinfunction "NC_1") (pintype "bidirectional"))
      (node (ref "R8") (pin "1") (pinfunction "1_1") (pintype "passive"))
      (node (ref "U1") (pin "C16") (pinfunction "MMC0_DAT2_C16") (pintype "bidirectional"))
    )
    (net (code "149") (name "SDMMC_D3") (class "Default")
      (node (ref "MICROSD_CARD") (pin "2") (pinfunction "/CS_2") (pintype "bidirectional"))
      (node (ref "R9") (pin "1") (pinfunction "1_1") (pintype "passive"))
      (node (ref "U1") (pin "C15") (pinfunction "MMC0_DAT3_C15") (pintype "bidirectional"))
    )
    (net (code "150") (name "SOL+") (class "Default")
      (node (ref "PILHA") (pin "7") (pinfunction "7_7") (pintype "passive"))
    )
    (net (code "151") (name "SOL-") (class "Default")
      (node (ref "PILHA") (pin "8") (pinfunction "8_8") (pintype "passive"))
    )
    (net (code "152") (name "SPI0_CS0") (class "Default")
      (node (ref "U1") (pin "A14") (pinfunction "SPI0_CS0_A14") (pintype "bidirectional"))
    )
    (net (code "153") (name "SPI0_CS1") (class "Default")
      (node (ref "U1") (pin "C14") (pinfunction "SPI0_CS1_C14") (pintype "bidirectional"))
    )
    (net (code "154") (name "SPI0_MISO") (class "Default")
      (node (ref "U1") (pin "B13") (pinfunction "SPI0_D0_B13") (pintype "bidirectional"))
    )
    (net (code "155") (name "SPI0_MOSI") (class "Default")
      (node (ref "U1") (pin "B14") (pinfunction "SPI0_D1_B14") (pintype "bidirectional"))
    )
    (net (code "156") (name "SPI0_SCLK") (class "Default")
      (node (ref "U1") (pin "A13") (pinfunction "SPI0_SCLK_A13") (pintype "bidirectional"))
    )
    (net (code "157") (name "SYS_VOUT") (class "Default")
      (node (ref "C20") (pin "1") (pinfunction "1_1") (pintype "passive"))
      (node (ref "U1") (pin "K6") (pinfunction "SYS_VOUT_K6") (pintype "power_in"))
      (node (ref "U1") (pin "K7") (pinfunction "SYS_VOUT_K7") (pintype "power_in"))
      (node (ref "U1") (pin "L6") (pinfunction "SYS_VOUT_L6") (pintype "power_in"))
      (node (ref "U1") (pin "L7") (pinfunction "SYS_VOUT_L7") (pintype "power_in"))
    )
    (net (code "158") (name "TCK") (class "Default")
      (node (ref "U1") (pin "D1") (pinfunction "TCK_D1") (pintype "bidirectional"))
    )
    (net (code "159") (name "TDI") (class "Default")
      (node (ref "U1") (pin "C1") (pinfunction "TDI_C1") (pintype "bidirectional"))
    )
    (net (code "160") (name "TDO") (class "Default")
      (node (ref "U1") (pin "C2") (pinfunction "TDO_C2") (pintype "bidirectional"))
    )
    (net (code "161") (name "TMS") (class "Default")
      (node (ref "U1") (pin "D2") (pinfunction "TMS_D2") (pintype "bidirectional"))
    )
    (net (code "162") (name "TRSTN") (class "Default")
      (node (ref "U1") (pin "D3") (pinfunction "TRSTN_D3") (pintype "bidirectional"))
    )
    (net (code "163") (name "TX1") (class "Default")
      (node (ref "PILHA") (pin "27") (pinfunction "27_27") (pintype "passive"))
      (node (ref "U1") (pin "R16") (pinfunction "GPMC_WPN_R16") (pintype "bidirectional"))
      (node (ref "U2") (pin "10") (pinfunction "10-RX_10") (pintype "bidirectional"))
    )
    (net (code "164") (name "TX2") (class "Default")
      (node (ref "PILHA") (pin "29") (pinfunction "29_29") (pintype "passive"))
    )
    (net (code "165") (name "UART0_RX") (class "Default")
      (node (ref "ESP-01") (pin "1") (pinfunction "1_1") (pintype "passive"))
      (node (ref "U1") (pin "A12") (pinfunction "UART0_RXD_A12") (pintype "bidirectional"))
    )
    (net (code "166") (name "UART0_TX") (class "Default")
      (node (ref "ESP-01") (pin "8") (pinfunction "8_8") (pintype "passive"))
      (node (ref "U1") (pin "B12") (pinfunction "UART0_TXD_B12") (pintype "bidirectional"))
    )
    (net (code "167") (name "USR0") (class "Default")
      (node (ref "U1") (pin "P13") (pinfunction "GPMC_A5_P13") (pintype "bidirectional"))
    )
    (net (code "168") (name "USR1") (class "Default")
      (node (ref "U1") (pin "T14") (pinfunction "GPMC_A6_T14") (pintype "bidirectional"))
    )
    (net (code "169") (name "USR2") (class "Default")
      (node (ref "U1") (pin "R14") (pinfunction "GPMC_A7_R14") (pintype "bidirectional"))
    )
    (net (code "170") (name "USR3") (class "Default")
      (node (ref "U1") (pin "P14") (pinfunction "GPMC_A8_P14") (pintype "bidirectional"))
    )
    (net (code "171") (name "VBUS1") (class "Default")
      (node (ref "C7") (pin "1") (pinfunction "1_1") (pintype "passive"))
      (node (ref "IC6") (pin "5") (pinfunction "VCC_5") (pintype "bidirectional"))
      (node (ref "U1") (pin "M15") (pinfunction "USB1_VBUS_M15") (pintype "bidirectional"))
      (node (ref "USB2") (pin "5") (pinfunction "S_5") (pintype "passive"))
    )
    (net (code "172") (name "VDD_RTC") (class "Default")
      (node (ref "C21") (pin "1") (pinfunction "1_1") (pintype "passive"))
      (node (ref "U1") (pin "K11") (pinfunction "SYS_RTC_1P8V_K11") (pintype "power_in"))
      (node (ref "U1") (pin "L11") (pinfunction "SYS_RTC_1P8V_L11") (pintype "power_in"))
      (node (ref "U4") (pin "5") (pinfunction "VCC_5") (pintype "bidirectional"))
    )
    (net (code "173") (name "VIN_BAT") (class "Default")
      (node (ref "U1") (pin "N7") (pinfunction "PMIC_BAT_SENSE_N7") (pintype "bidirectional"))
      (node (ref "U1") (pin "P8") (pinfunction "VIN_BAT_P8") (pintype "power_in"))
      (node (ref "U1") (pin "R8") (pinfunction "VIN_BAT_R8") (pintype "power_in"))
      (node (ref "U1") (pin "T8") (pinfunction "VIN_BAT_T8") (pintype "power_in"))
    )
    (net (code "174") (name "VIN_USB") (class "Default")
      (node (ref "C2") (pin "1") (pinfunction "1_1") (pintype "passive"))
      (node (ref "IC2") (pin "5") (pinfunction "VCC_5") (pintype "bidirectional"))
      (node (ref "U1") (pin "J16") (pinfunction "USB0_VBUS_J16") (pintype "bidirectional"))
      (node (ref "U1") (pin "P9") (pinfunction "VIN_USB_P9") (pintype "power_in"))
      (node (ref "U1") (pin "R9") (pinfunction "VIN_USB_R9") (pintype "power_in"))
      (node (ref "U1") (pin "T9") (pinfunction "VIN_USB_T9") (pintype "power_in"))
      (node (ref "USB1") (pin "5") (pinfunction "S_5") (pintype "passive"))
    )
    (net (code "175") (name "unconnected-(IC1-S-Pad8)") (class "Default")
      (node (ref "IC1") (pin "8") (pinfunction "S_8") (pintype "bidirectional"))
    )
    (net (code "176") (name "unconnected-(IC1-SHDN-Pad5)") (class "Default")
      (node (ref "IC1") (pin "5") (pinfunction "SHDN_5") (pintype "bidirectional"))
    )
    (net (code "177") (name "unconnected-(IC2-D2--Pad4)") (class "Default")
      (node (ref "IC2") (pin "4") (pinfunction "D2-_4") (pintype "bidirectional"))
    )
    (net (code "178") (name "unconnected-(IC3-CLKOUT-Pad3)") (class "Default")
      (node (ref "IC3") (pin "3") (pinfunction "CLKOUT_3") (pintype "output"))
    )
    (net (code "179") (name "unconnected-(IC3-~{RX0BF}-Pad11)") (class "Default")
      (node (ref "IC3") (pin "11") (pinfunction "~{RX0BF}_11") (pintype "bidirectional"))
    )
    (net (code "180") (name "unconnected-(IC3-~{RX1BF}-Pad10)") (class "Default")
      (node (ref "IC3") (pin "10") (pinfunction "~{RX1BF}_10") (pintype "bidirectional"))
    )
    (net (code "181") (name "unconnected-(IC3-~{TX0RTS}-Pad4)") (class "Default")
      (node (ref "IC3") (pin "4") (pinfunction "~{TX0RTS}_4") (pintype "bidirectional"))
    )
    (net (code "182") (name "unconnected-(IC3-~{TX1RTS}-Pad5)") (class "Default")
      (node (ref "IC3") (pin "5") (pinfunction "~{TX1RTS}_5") (pintype "bidirectional"))
    )
    (net (code "183") (name "unconnected-(IC3-~{TX2RTS}-Pad6)") (class "Default")
      (node (ref "IC3") (pin "6") (pinfunction "~{TX2RTS}_6") (pintype "bidirectional"))
    )
    (net (code "184") (name "unconnected-(IC5-S-Pad8)") (class "Default")
      (node (ref "IC5") (pin "8") (pinfunction "S_8") (pintype "bidirectional"))
    )
    (net (code "185") (name "unconnected-(IC5-SHDN-Pad5)") (class "Default")
      (node (ref "IC5") (pin "5") (pinfunction "SHDN_5") (pintype "bidirectional"))
    )
    (net (code "186") (name "unconnected-(IC6-D2--Pad4)") (class "Default")
      (node (ref "IC6") (pin "4") (pinfunction "D2-_4") (pintype "bidirectional"))
    )
    (net (code "187") (name "unconnected-(IC9-S-Pad8)") (class "Default")
      (node (ref "IC9") (pin "8") (pinfunction "S_8") (pintype "bidirectional"))
    )
    (net (code "188") (name "unconnected-(IC9-SHDN-Pad5)") (class "Default")
      (node (ref "IC9") (pin "5") (pinfunction "SHDN_5") (pintype "bidirectional"))
    )
    (net (code "189") (name "unconnected-(U1A-PMIC_NRESET-PadM13)") (class "Default")
      (node (ref "U1") (pin "M13") (pinfunction "PMIC_NRESET_M13") (pintype "bidirectional"))
    )
    (net (code "190") (name "unconnected-(U1C-ECAP0_IN_PWM0_OUT-PadC5)") (class "Default")
      (node (ref "U1") (pin "C5") (pinfunction "ECAP0_IN_PWM0_OUT_C5") (pintype "bidirectional"))
    )
    (net (code "191") (name "unconnected-(U1C-GPMC_A0-PadT12)") (class "Default")
      (node (ref "U1") (pin "T12") (pinfunction "GPMC_A0_T12") (pintype "bidirectional"))
    )
    (net (code "192") (name "unconnected-(U1C-GPMC_A1-PadR12)") (class "Default")
      (node (ref "U1") (pin "R12") (pinfunction "GPMC_A1_R12") (pintype "bidirectional"))
    )
    (net (code "193") (name "unconnected-(U1C-GPMC_A3-PadT13)") (class "Default")
      (node (ref "U1") (pin "T13") (pinfunction "GPMC_A3_T13") (pintype "bidirectional"))
    )
    (net (code "194") (name "unconnected-(U1C-GPMC_AD0-PadR3)") (class "Default")
      (node (ref "U1") (pin "R3") (pinfunction "GPMC_AD0_R3") (pintype "bidirectional"))
    )
    (net (code "195") (name "unconnected-(U1C-GPMC_AD1-PadR2)") (class "Default")
      (node (ref "U1") (pin "R2") (pinfunction "GPMC_AD1_R2") (pintype "bidirectional"))
    )
    (net (code "196") (name "unconnected-(U1C-GPMC_AD2-PadR1)") (class "Default")
      (node (ref "U1") (pin "R1") (pinfunction "GPMC_AD2_R1") (pintype "bidirectional"))
    )
    (net (code "197") (name "unconnected-(U1C-GPMC_AD3-PadT3)") (class "Default")
      (node (ref "U1") (pin "T3") (pinfunction "GPMC_AD3_T3") (pintype "bidirectional"))
    )
    (net (code "198") (name "unconnected-(U1C-GPMC_AD4-PadT2)") (class "Default")
      (node (ref "U1") (pin "T2") (pinfunction "GPMC_AD4_T2") (pintype "bidirectional"))
    )
    (net (code "199") (name "unconnected-(U1C-GPMC_AD5-PadT1)") (class "Default")
      (node (ref "U1") (pin "T1") (pinfunction "GPMC_AD5_T1") (pintype "bidirectional"))
    )
    (net (code "200") (name "unconnected-(U1C-GPMC_AD6-PadP4)") (class "Default")
      (node (ref "U1") (pin "P4") (pinfunction "GPMC_AD6_P4") (pintype "bidirectional"))
    )
    (net (code "201") (name "unconnected-(U1C-GPMC_AD7-PadR4)") (class "Default")
      (node (ref "U1") (pin "R4") (pinfunction "GPMC_AD7_R4") (pintype "bidirectional"))
    )
    (net (code "202") (name "unconnected-(U1C-GPMC_AD8-PadT4)") (class "Default")
      (node (ref "U1") (pin "T4") (pinfunction "GPMC_AD8_T4") (pintype "bidirectional"))
    )
    (net (code "203") (name "unconnected-(U1C-GPMC_ADVN_ALE-PadM1)") (class "Default")
      (node (ref "U1") (pin "M1") (pinfunction "GPMC_ADVN_ALE_M1") (pintype "bidirectional"))
    )
    (net (code "204") (name "unconnected-(U1C-GPMC_CSN0-PadP3)") (class "Default")
      (node (ref "U1") (pin "P3") (pinfunction "GPMC_CSN0_P3") (pintype "bidirectional"))
    )
    (net (code "205") (name "unconnected-(U1C-GPMC_CSN1-PadP2)") (class "Default")
      (node (ref "U1") (pin "P2") (pinfunction "GPMC_CSN1_P2") (pintype "bidirectional"))
    )
    (net (code "206") (name "unconnected-(U1C-GPMC_CSN2-PadP1)") (class "Default")
      (node (ref "U1") (pin "P1") (pinfunction "GPMC_CSN2_P1") (pintype "bidirectional"))
    )
    (net (code "207") (name "unconnected-(U1C-GPMC_OEN_REN-PadN1)") (class "Default")
      (node (ref "U1") (pin "N1") (pinfunction "GPMC_OEN_REN_N1") (pintype "bidirectional"))
    )
    (net (code "208") (name "unconnected-(U1C-GPMC_WEN-PadN2)") (class "Default")
      (node (ref "U1") (pin "N2") (pinfunction "GPMC_WEN_N2") (pintype "bidirectional"))
    )
    (net (code "209") (name "unconnected-(U1C-XDMA_EVENT_INTR0-PadA4)") (class "Default")
      (node (ref "U1") (pin "A4") (pinfunction "XDMA_EVENT_INTR0_A4") (pintype "bidirectional"))
    )
    (net (code "210") (name "unconnected-(U1D-LCD_VSYNC-PadF3)") (class "Default")
      (node (ref "U1") (pin "F3") (pinfunction "LCD_VSYNC_F3") (pintype "bidirectional"))
    )
    (net (code "211") (name "unconnected-(U1D-MDC-PadD13)") (class "Default")
      (node (ref "U1") (pin "D13") (pinfunction "MDC_D13") (pintype "bidirectional"))
    )
    (net (code "212") (name "unconnected-(U1D-MDIO-PadE13)") (class "Default")
      (node (ref "U1") (pin "E13") (pinfunction "MDIO_E13") (pintype "bidirectional"))
    )
    (net (code "213") (name "unconnected-(U1D-MII1_COL-PadF15)") (class "Default")
      (node (ref "U1") (pin "F15") (pinfunction "MII1_COL_F15") (pintype "bidirectional"))
    )
    (net (code "214") (name "unconnected-(U1D-MII1_CRS-PadF14)") (class "Default")
      (node (ref "U1") (pin "F14") (pinfunction "MII1_CRS_F14") (pintype "bidirectional"))
    )
    (net (code "215") (name "unconnected-(U1D-MII1_RXD0-PadE14)") (class "Default")
      (node (ref "U1") (pin "E14") (pinfunction "MII1_RXD0_E14") (pintype "bidirectional"))
    )
    (net (code "216") (name "unconnected-(U1D-MII1_RXD1-PadD16)") (class "Default")
      (node (ref "U1") (pin "D16") (pinfunction "MII1_RXD1_D16") (pintype "bidirectional"))
    )
    (net (code "217") (name "unconnected-(U1D-MII1_RXD2-PadD15)") (class "Default")
      (node (ref "U1") (pin "D15") (pinfunction "MII1_RXD2_D15") (pintype "bidirectional"))
    )
    (net (code "218") (name "unconnected-(U1D-MII1_RXD3-PadD14)") (class "Default")
      (node (ref "U1") (pin "D14") (pinfunction "MII1_RXD3_D14") (pintype "bidirectional"))
    )
    (net (code "219") (name "unconnected-(U1D-MII1_RX_CLK-PadE16)") (class "Default")
      (node (ref "U1") (pin "E16") (pinfunction "MII1_RX_CLK_E16") (pintype "bidirectional"))
    )
    (net (code "220") (name "unconnected-(U1D-MII1_RX_DV-PadF16)") (class "Default")
      (node (ref "U1") (pin "F16") (pinfunction "MII1_RX_DV_F16") (pintype "bidirectional"))
    )
    (net (code "221") (name "unconnected-(U1D-MII1_RX_ER-PadE15)") (class "Default")
      (node (ref "U1") (pin "E15") (pinfunction "MII1_RX_ER_E15") (pintype "bidirectional"))
    )
    (net (code "222") (name "unconnected-(U1D-MII1_TXD0-PadH15)") (class "Default")
      (node (ref "U1") (pin "H15") (pinfunction "MII1_TXD0_H15") (pintype "bidirectional"))
    )
    (net (code "223") (name "unconnected-(U1D-MII1_TXD1-PadH14)") (class "Default")
      (node (ref "U1") (pin "H14") (pinfunction "MII1_TXD1_H14") (pintype "bidirectional"))
    )
    (net (code "224") (name "unconnected-(U1D-MII1_TXD2-PadG16)") (class "Default")
      (node (ref "U1") (pin "G16") (pinfunction "MII1_TXD2_G16") (pintype "bidirectional"))
    )
    (net (code "225") (name "unconnected-(U1D-MII1_TXD3-PadG15)") (class "Default")
      (node (ref "U1") (pin "G15") (pinfunction "MII1_TXD3_G15") (pintype "bidirectional"))
    )
    (net (code "226") (name "unconnected-(U1D-MII1_TX_CLK-PadH16)") (class "Default")
      (node (ref "U1") (pin "H16") (pinfunction "MII1_TX_CLK_H16") (pintype "bidirectional"))
    )
    (net (code "227") (name "unconnected-(U1D-MII1_TX_EN-PadG14)") (class "Default")
      (node (ref "U1") (pin "G14") (pinfunction "MII1_TX_EN_G14") (pintype "bidirectional"))
    )
    (net (code "228") (name "unconnected-(U1D-RMII1_REF_CLK-PadJ14)") (class "Default")
      (node (ref "U1") (pin "J14") (pinfunction "RMII1_REF_CLK_J14") (pintype "bidirectional"))
    )
    (net (code "229") (name "unconnected-(U1F-CAP_VDD_RTC-PadD5)") (class "Default")
      (node (ref "U1") (pin "D5") (pinfunction "CAP_VDD_RTC_D5") (pintype "bidirectional"))
    )
    (net (code "230") (name "unconnected-(U1F-NC-PadD12)") (class "Default")
      (node (ref "U1") (pin "D12") (pinfunction "NC_D12") (pintype "bidirectional"))
    )
    (net (code "231") (name "unconnected-(U1F-NC-PadJ6)") (class "Default")
      (node (ref "U1") (pin "J6") (pinfunction "NC_J6") (pintype "bidirectional"))
    )
    (net (code "232") (name "unconnected-(U1F-NC-PadK4)") (class "Default")
      (node (ref "U1") (pin "K4") (pinfunction "NC_K4") (pintype "bidirectional"))
    )
    (net (code "233") (name "unconnected-(U1F-VDDS_DDR-PadF4)") (class "Default")
      (node (ref "U1") (pin "F4") (pinfunction "VDDS_DDR_F4") (pintype "bidirectional"))
    )
    (net (code "234") (name "unconnected-(U1F-VDDS_PLL-PadG13)") (class "Default")
      (node (ref "U1") (pin "G13") (pinfunction "VDDS_PLL_G13") (pintype "bidirectional"))
    )
    (net (code "235") (name "unconnected-(U1F-VDD_CORE-PadG4)") (class "Default")
      (node (ref "U1") (pin "G4") (pinfunction "VDD_CORE_G4") (pintype "bidirectional"))
    )
    (net (code "236") (name "unconnected-(U1F-VDD_MPU-PadF13)") (class "Default")
      (node (ref "U1") (pin "F13") (pinfunction "VDD_MPU_F13") (pintype "bidirectional"))
    )
    (net (code "237") (name "unconnected-(U1F-VPP-PadH6)") (class "Default")
      (node (ref "U1") (pin "H6") (pinfunction "VPP_H6") (pintype "bidirectional"))
    )
  )
)
